# shield.net
KiCad netlist of a schematic drawn in EAGLE
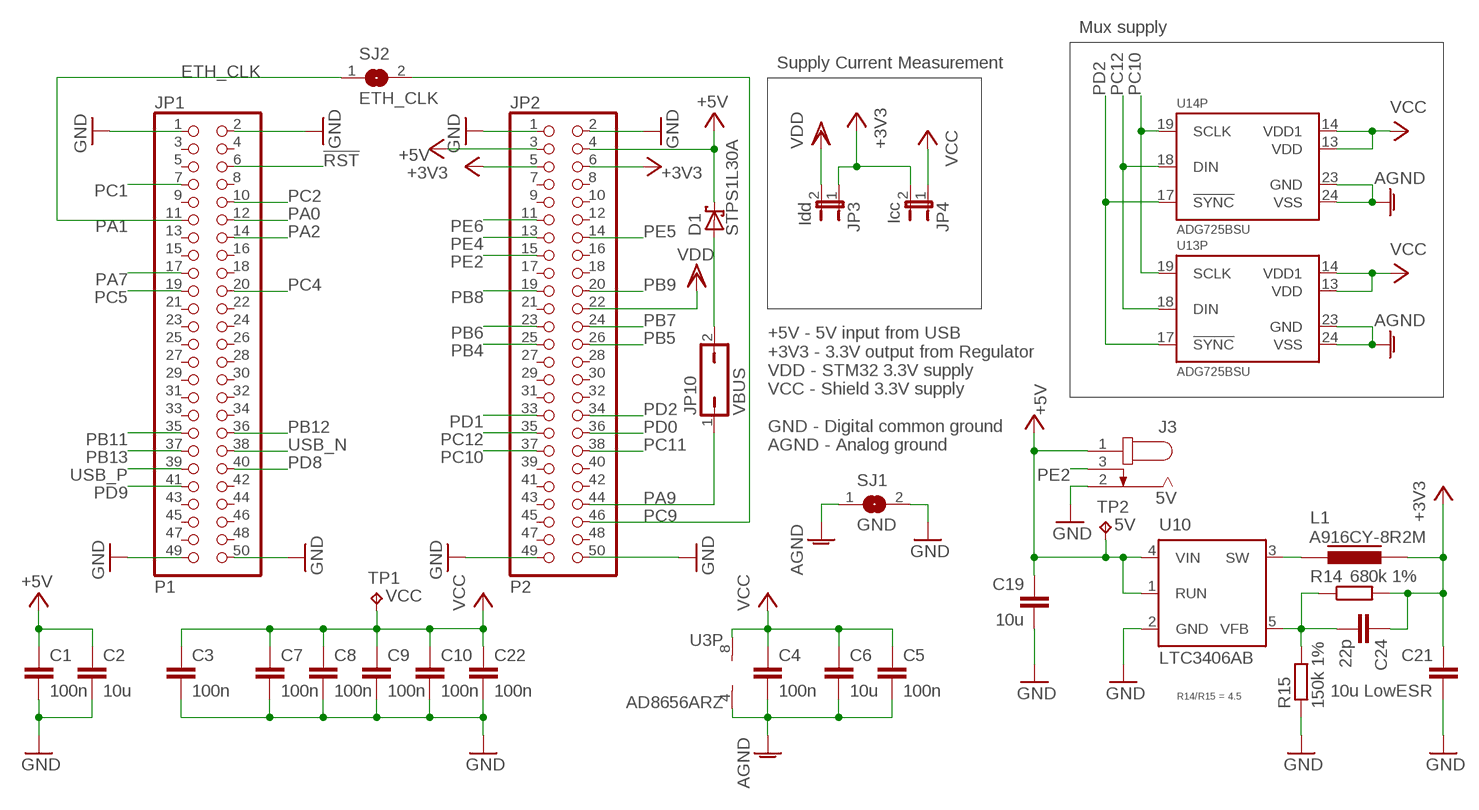
[diagram p0: schematic, sheet 1]
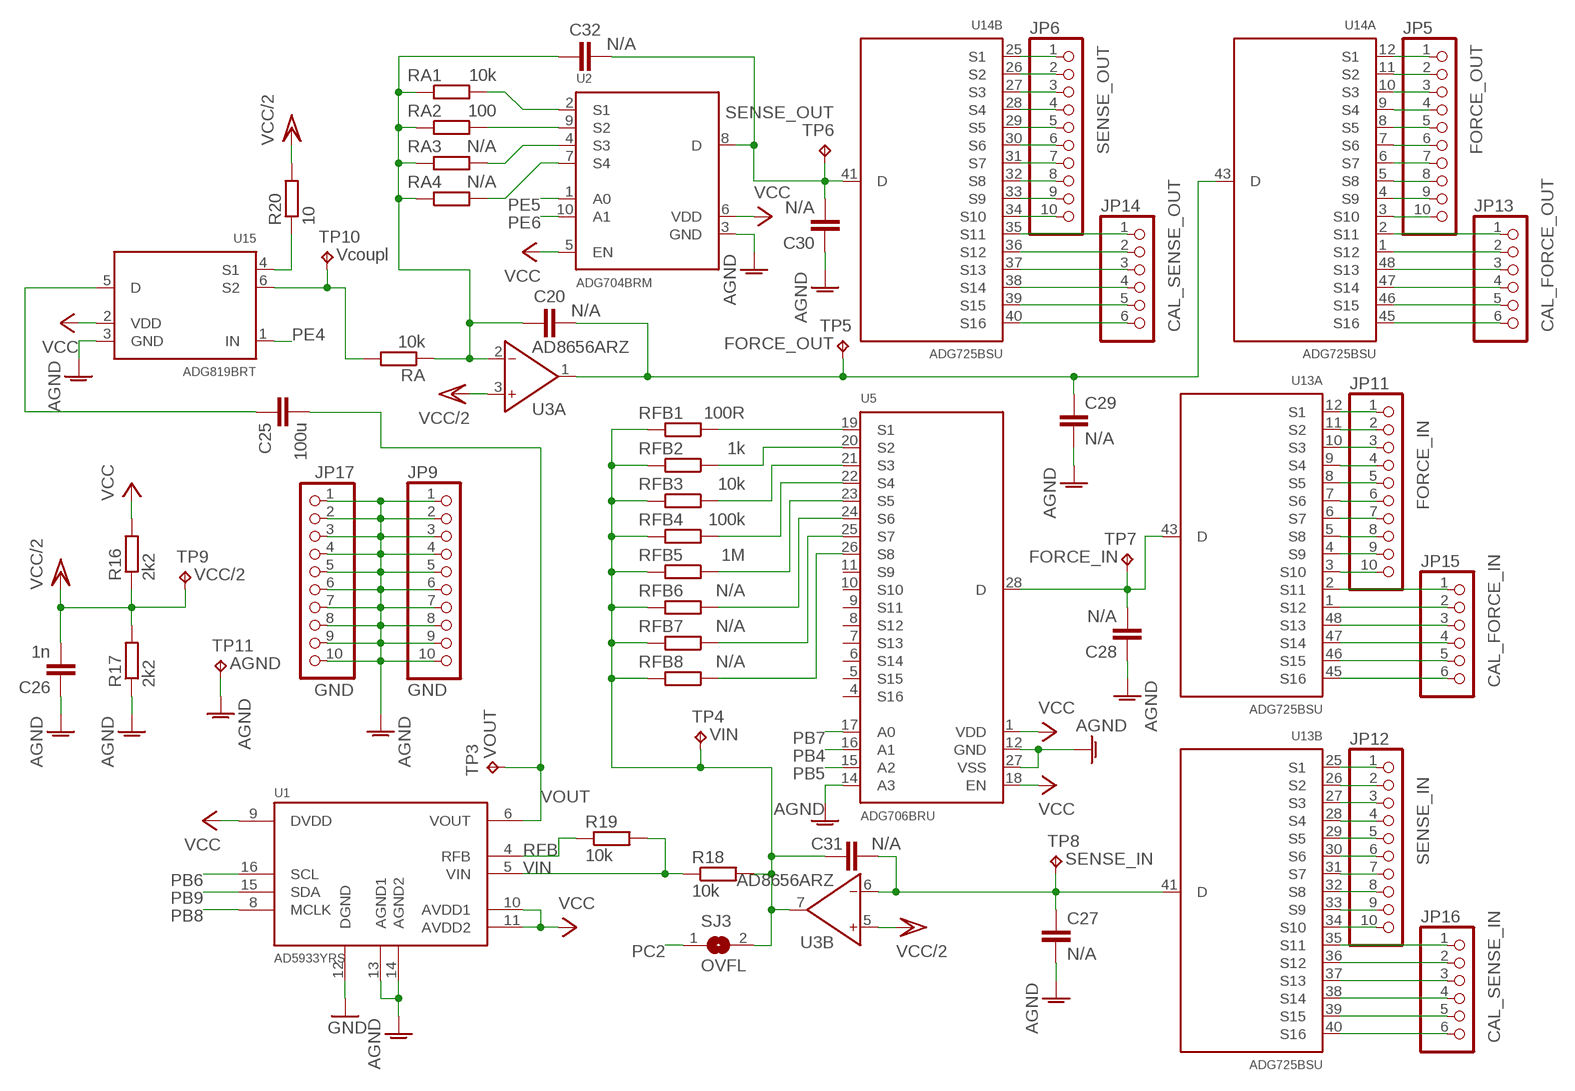
[diagram p1: schematic, sheet 2]
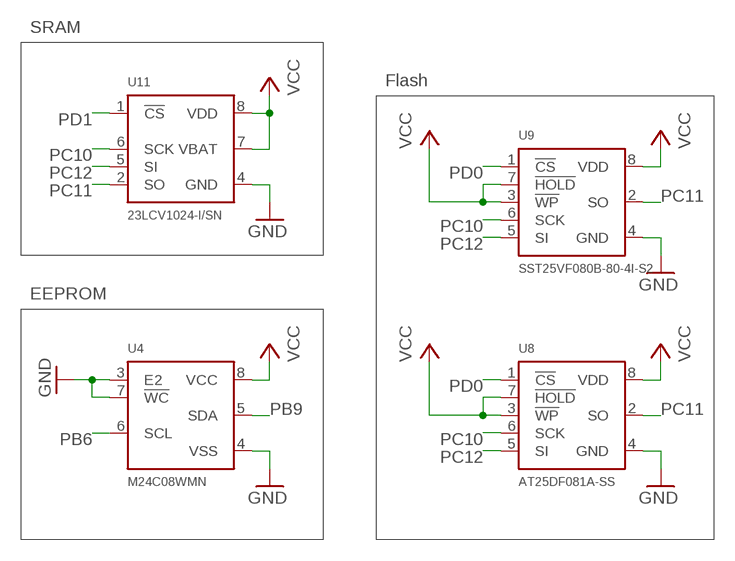
[diagram p2: schematic, sheet 3]
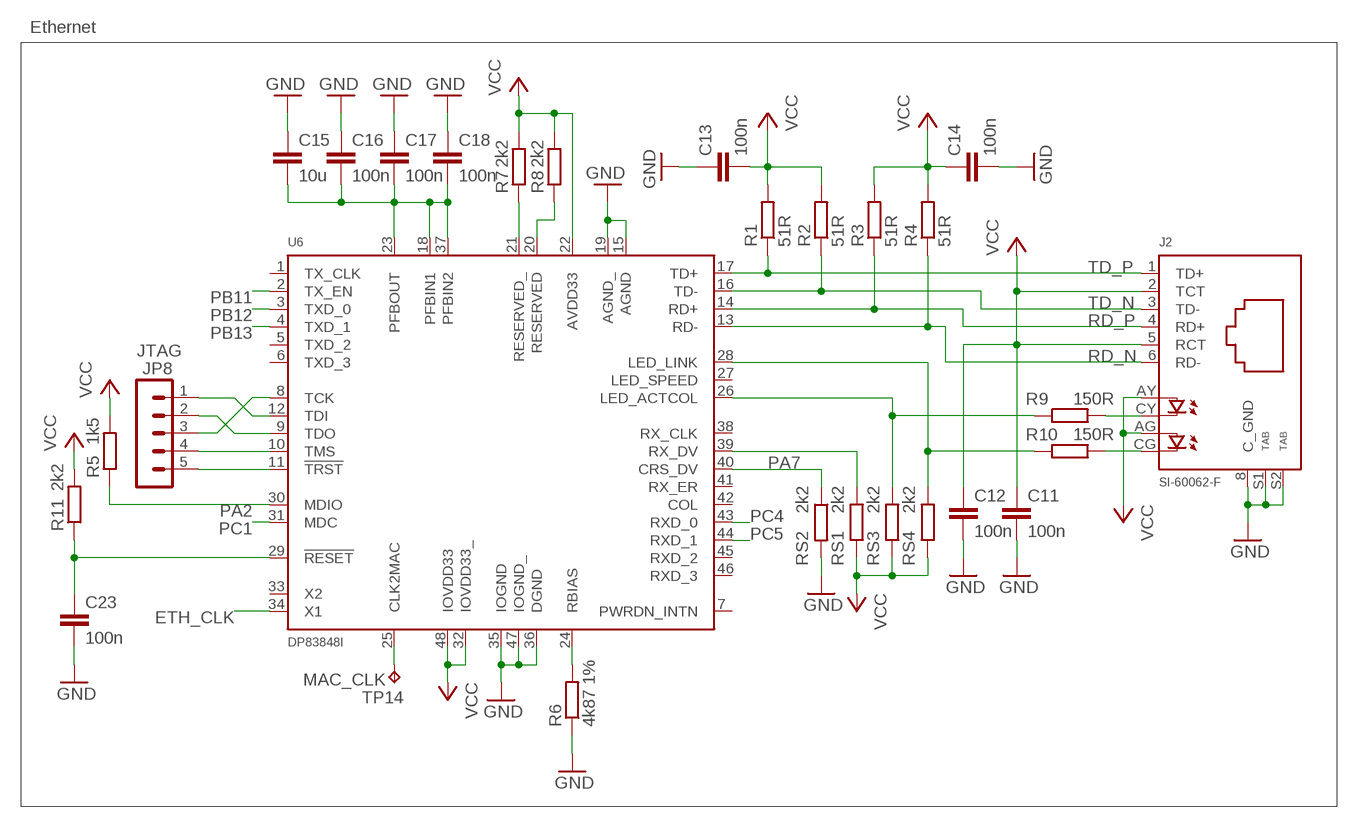
[diagram p3: schematic, sheet 4]
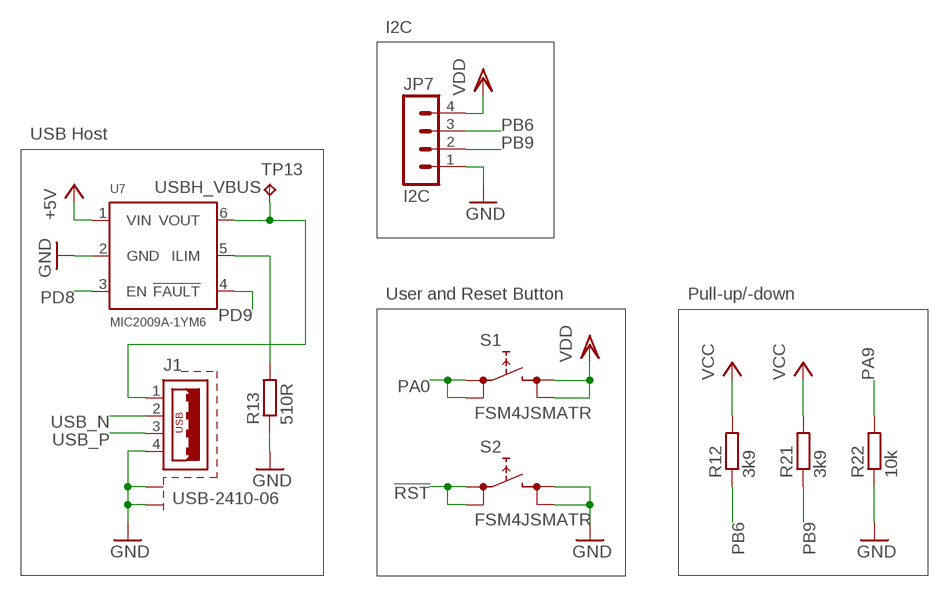
[diagram p4: schematic, sheet 5]

(export (version "E")
  (design (tool "Eeschema 10.0.6"))
  (components
    (comp (ref "J1")
      (value "USB-2410-06")
      (footprint "eagle-import:USB-2410-06")
      (libsource (lib "eagle-import") (part "USB-2410-06"))
    )
    (comp (ref "JP7")
      (value "I2C")
      (footprint "eagle-import:MA04-1")
      (libsource (lib "eagle-import") (part "MA04-1"))
    )
    (comp (ref "R12")
      (value "3k9")
      (footprint "eagle-import:R0603")
      (libsource (lib "eagle-import") (part "R-EU_R0603"))
    )
    (comp (ref "R13")
      (value "510R")
      (footprint "eagle-import:R0603")
      (libsource (lib "eagle-import") (part "R-EU_R0603"))
    )
    (comp (ref "R21")
      (value "3k9")
      (footprint "eagle-import:R0603")
      (libsource (lib "eagle-import") (part "R-EU_R0603"))
    )
    (comp (ref "R22")
      (value "10k")
      (footprint "eagle-import:R0603")
      (libsource (lib "eagle-import") (part "R-EU_R0603"))
    )
    (comp (ref "S1")
      (value "FSM4JSMATR")
      (footprint "eagle-import:FSM")
      (libsource (lib "eagle-import") (part "FSM4JSMATR"))
    )
    (comp (ref "S2")
      (value "FSM4JSMATR")
      (footprint "eagle-import:FSM")
      (libsource (lib "eagle-import") (part "FSM4JSMATR"))
    )
    (comp (ref "TP13")
      (value "TPTP20R")
      (footprint "eagle-import:TP20R")
      (fields (field (name "TP_SIGNAL_NAME") "USBH_VBUS"))
      (libsource (lib "eagle-import") (part "TPTP20R"))
    )
    (comp (ref "U7")
      (value "MIC2009A-1YM6")
      (footprint "eagle-import:SOT23-6")
      (libsource (lib "eagle-import") (part "MIC2009A-1YM6"))
    )
    (comp (ref "C1")
      (value "100n")
      (footprint "eagle-import:C0603")
      (libsource (lib "eagle-import") (part "C-EUC0603"))
    )
    (comp (ref "C2")
      (value "10u")
      (footprint "eagle-import:C0603")
      (libsource (lib "eagle-import") (part "C-EUC0603"))
    )
    (comp (ref "C3")
      (value "100n")
      (footprint "eagle-import:C0603")
      (libsource (lib "eagle-import") (part "C-EUC0603"))
    )
    (comp (ref "C4")
      (value "100n")
      (footprint "eagle-import:C0603")
      (libsource (lib "eagle-import") (part "C-EUC0603"))
    )
    (comp (ref "C5")
      (value "100n")
      (footprint "eagle-import:C0603")
      (libsource (lib "eagle-import") (part "C-EUC0603"))
    )
    (comp (ref "C6")
      (value "10u")
      (footprint "eagle-import:C0603")
      (libsource (lib "eagle-import") (part "C-EUC0603"))
    )
    (comp (ref "C7")
      (value "100n")
      (footprint "eagle-import:C0603")
      (libsource (lib "eagle-import") (part "C-EUC0603"))
    )
    (comp (ref "C8")
      (value "100n")
      (footprint "eagle-import:C0603")
      (libsource (lib "eagle-import") (part "C-EUC0603"))
    )
    (comp (ref "C9")
      (value "100n")
      (footprint "eagle-import:C0603")
      (libsource (lib "eagle-import") (part "C-EUC0603"))
    )
    (comp (ref "C10")
      (value "100n")
      (footprint "eagle-import:C0603")
      (libsource (lib "eagle-import") (part "C-EUC0603"))
    )
    (comp (ref "C19")
      (value "10u")
      (footprint "eagle-import:C3216")
      (libsource (lib "eagle-import") (part "C-EUC3216"))
    )
    (comp (ref "C21")
      (value "10u LowESR")
      (footprint "eagle-import:C3216")
      (libsource (lib "eagle-import") (part "C-EUC3216"))
    )
    (comp (ref "C22")
      (value "100n")
      (footprint "eagle-import:C0603")
      (libsource (lib "eagle-import") (part "C-EUC0603"))
    )
    (comp (ref "C24")
      (value "22p")
      (footprint "eagle-import:C0603")
      (libsource (lib "eagle-import") (part "C-EUC0603"))
    )
    (comp (ref "D1")
      (value "STPS1L30A")
      (footprint "eagle-import:DO214AC")
      (libsource (lib "eagle-import") (part "STPS1L30A"))
    )
    (comp (ref "J3")
      (value "5V")
      (footprint "eagle-import:JACK-SMD2.5")
      (libsource (lib "eagle-import") (part "JACK-PLUG-S2.5"))
    )
    (comp (ref "JP1")
      (value "P1")
      (footprint "eagle-import:2X25-F")
      (libsource (lib "eagle-import") (part "PINHD-2X25-F"))
    )
    (comp (ref "JP2")
      (value "P2")
      (footprint "eagle-import:2X25-F")
      (libsource (lib "eagle-import") (part "PINHD-2X25-F"))
    )
    (comp (ref "JP3")
      (value "Idd")
      (footprint "eagle-import:JP1")
      (libsource (lib "eagle-import") (part "JP1E"))
    )
    (comp (ref "JP4")
      (value "Icc")
      (footprint "eagle-import:JP1")
      (libsource (lib "eagle-import") (part "JP1E"))
    )
    (comp (ref "JP10")
      (value "VBUS")
      (footprint "eagle-import:JP1")
      (libsource (lib "eagle-import") (part "JP1Q"))
    )
    (comp (ref "L1")
      (value "A916CY-8R2M")
      (footprint "eagle-import:D63CB")
      (libsource (lib "eagle-import") (part "A916CY-8R2M"))
    )
    (comp (ref "R14")
      (value "680k 1%")
      (footprint "eagle-import:R0603")
      (libsource (lib "eagle-import") (part "R-EU_R0603"))
    )
    (comp (ref "R15")
      (value "150k 1%")
      (footprint "eagle-import:R0603")
      (libsource (lib "eagle-import") (part "R-EU_R0603"))
    )
    (comp (ref "SJ1")
      (value "GND")
      (footprint "eagle-import:SJ")
      (libsource (lib "eagle-import") (part "SJ"))
    )
    (comp (ref "SJ2")
      (value "ETH_CLK")
      (footprint "eagle-import:SJ")
      (libsource (lib "eagle-import") (part "SJ"))
    )
    (comp (ref "TP1")
      (value "TPTP20R")
      (footprint "eagle-import:TP20R")
      (fields (field (name "TP_SIGNAL_NAME") "VCC"))
      (libsource (lib "eagle-import") (part "TPTP20R"))
    )
    (comp (ref "TP2")
      (value "TPTP20R")
      (footprint "eagle-import:TP20R")
      (fields (field (name "TP_SIGNAL_NAME") "5V"))
      (libsource (lib "eagle-import") (part "TPTP20R"))
    )
    (comp (ref "U3")
      (value "AD8656ARZ")
      (footprint "eagle-import:SOIC8")
      (libsource (lib "eagle-import") (part "AD8656ZAR"))
    )
    (comp (ref "U10")
      (value "LTC3406AB")
      (footprint "eagle-import:TSOT23-5")
      (libsource (lib "eagle-import") (part "LTC3406AB"))
    )
    (comp (ref "U13")
      (value "ADG725BSU")
      (footprint "eagle-import:TQFP48")
      (libsource (lib "eagle-import") (part "ADG725SUB"))
    )
    (comp (ref "U14")
      (value "ADG725BSU")
      (footprint "eagle-import:TQFP48")
      (libsource (lib "eagle-import") (part "ADG725SUB"))
    )
    (comp (ref "C11")
      (value "100n")
      (footprint "eagle-import:C0603")
      (libsource (lib "eagle-import") (part "C-EUC0603"))
    )
    (comp (ref "C12")
      (value "100n")
      (footprint "eagle-import:C0603")
      (libsource (lib "eagle-import") (part "C-EUC0603"))
    )
    (comp (ref "C13")
      (value "100n")
      (footprint "eagle-import:C0603")
      (libsource (lib "eagle-import") (part "C-EUC0603"))
    )
    (comp (ref "C14")
      (value "100n")
      (footprint "eagle-import:C0603")
      (libsource (lib "eagle-import") (part "C-EUC0603"))
    )
    (comp (ref "C15")
      (value "10u")
      (footprint "eagle-import:C0603")
      (libsource (lib "eagle-import") (part "C-EUC0603"))
    )
    (comp (ref "C16")
      (value "100n")
      (footprint "eagle-import:C0603")
      (libsource (lib "eagle-import") (part "C-EUC0603"))
    )
    (comp (ref "C17")
      (value "100n")
      (footprint "eagle-import:C0603")
      (libsource (lib "eagle-import") (part "C-EUC0603"))
    )
    (comp (ref "C18")
      (value "100n")
      (footprint "eagle-import:C0603")
      (libsource (lib "eagle-import") (part "C-EUC0603"))
    )
    (comp (ref "C23")
      (value "100n")
      (footprint "eagle-import:C0603")
      (libsource (lib "eagle-import") (part "C-EUC0603"))
    )
    (comp (ref "J2")
      (value "SI-60062-F")
      (footprint "eagle-import:SI-60062-F")
      (libsource (lib "eagle-import") (part "SI-60062-F"))
    )
    (comp (ref "JP8")
      (value "JTAG")
      (footprint "eagle-import:MA05-1")
      (libsource (lib "eagle-import") (part "MA05-1"))
    )
    (comp (ref "R1")
      (value "51R")
      (footprint "eagle-import:R0603")
      (libsource (lib "eagle-import") (part "R-EU_R0603"))
    )
    (comp (ref "R2")
      (value "51R")
      (footprint "eagle-import:R0603")
      (libsource (lib "eagle-import") (part "R-EU_R0603"))
    )
    (comp (ref "R3")
      (value "51R")
      (footprint "eagle-import:R0603")
      (libsource (lib "eagle-import") (part "R-EU_R0603"))
    )
    (comp (ref "R4")
      (value "51R")
      (footprint "eagle-import:R0603")
      (libsource (lib "eagle-import") (part "R-EU_R0603"))
    )
    (comp (ref "R5")
      (value "1k5")
      (footprint "eagle-import:R0603")
      (libsource (lib "eagle-import") (part "R-EU_R0603"))
    )
    (comp (ref "R6")
      (value "4k87 1%")
      (footprint "eagle-import:R0603")
      (libsource (lib "eagle-import") (part "R-EU_R0603"))
    )
    (comp (ref "R7")
      (value "2k2")
      (footprint "eagle-import:R0603")
      (libsource (lib "eagle-import") (part "R-EU_R0603"))
    )
    (comp (ref "R8")
      (value "2k2")
      (footprint "eagle-import:R0603")
      (libsource (lib "eagle-import") (part "R-EU_R0603"))
    )
    (comp (ref "R9")
      (value "150R")
      (footprint "eagle-import:R0603")
      (libsource (lib "eagle-import") (part "R-EU_R0603"))
    )
    (comp (ref "R10")
      (value "150R")
      (footprint "eagle-import:R0603")
      (libsource (lib "eagle-import") (part "R-EU_R0603"))
    )
    (comp (ref "R11")
      (value "2k2")
      (footprint "eagle-import:R0603")
      (libsource (lib "eagle-import") (part "R-EU_R0603"))
    )
    (comp (ref "RS1")
      (value "2k2")
      (footprint "eagle-import:R0603")
      (libsource (lib "eagle-import") (part "R-EU_R0603"))
    )
    (comp (ref "RS2")
      (value "2k2")
      (footprint "eagle-import:R0603")
      (libsource (lib "eagle-import") (part "R-EU_R0603"))
    )
    (comp (ref "RS3")
      (value "2k2")
      (footprint "eagle-import:R0603")
      (libsource (lib "eagle-import") (part "R-EU_R0603"))
    )
    (comp (ref "RS4")
      (value "2k2")
      (footprint "eagle-import:R0603")
      (libsource (lib "eagle-import") (part "R-EU_R0603"))
    )
    (comp (ref "TP14")
      (value "TPTP20R")
      (footprint "eagle-import:TP20R")
      (fields (field (name "TP_SIGNAL_NAME") "MAC_CLK"))
      (libsource (lib "eagle-import") (part "TPTP20R"))
    )
    (comp (ref "U6")
      (value "DP83848I")
      (footprint "eagle-import:LQFP48")
      (fields (field (name "MPN") "DP83848IVV"))
      (libsource (lib "eagle-import") (part "DP83848I"))
    )
    (comp (ref "U4")
      (value "M24C08WMN")
      (footprint "eagle-import:SO8")
      (libsource (lib "eagle-import") (part "M24C08MNW"))
    )
    (comp (ref "U8")
      (value "AT25DF081A-SS")
      (footprint "eagle-import:SO8")
      (libsource (lib "eagle-import") (part "AT25DF081A-SS"))
    )
    (comp (ref "U9")
      (value "SST25VF080B-80-4I-S2")
      (footprint "eagle-import:SOIC8")
      (libsource (lib "eagle-import") (part "SST25VF080B-S2-80-4I"))
    )
    (comp (ref "U11")
      (value "23LCV1024-I/SN")
      (footprint "eagle-import:SO8")
      (libsource (lib "eagle-import") (part "23LCV1024/SN-I"))
    )
    (comp (ref "C20")
      (value "N/A")
      (footprint "eagle-import:C0603")
      (libsource (lib "eagle-import") (part "C-EUC0603"))
    )
    (comp (ref "C25")
      (value "100u")
      (footprint "eagle-import:C1206")
      (libsource (lib "eagle-import") (part "C-EUC1206"))
    )
    (comp (ref "C26")
      (value "1n")
      (footprint "eagle-import:C0603")
      (libsource (lib "eagle-import") (part "C-EUC0603"))
    )
    (comp (ref "C27")
      (value "N/A")
      (footprint "eagle-import:C0805")
      (libsource (lib "eagle-import") (part "C-EUC0805"))
    )
    (comp (ref "C28")
      (value "N/A")
      (footprint "eagle-import:C0805")
      (libsource (lib "eagle-import") (part "C-EUC0805"))
    )
    (comp (ref "C29")
      (value "N/A")
      (footprint "eagle-import:C0805")
      (libsource (lib "eagle-import") (part "C-EUC0805"))
    )
    (comp (ref "C30")
      (value "N/A")
      (footprint "eagle-import:C0805")
      (libsource (lib "eagle-import") (part "C-EUC0805"))
    )
    (comp (ref "C31")
      (value "N/A")
      (footprint "eagle-import:C0603")
      (libsource (lib "eagle-import") (part "C-EUC0603"))
    )
    (comp (ref "C32")
      (value "N/A")
      (footprint "eagle-import:C0603")
      (libsource (lib "eagle-import") (part "C-EUC0603"))
    )
    (comp (ref "JP5")
      (value "FORCE_OUT")
      (footprint "eagle-import:1X10")
      (libsource (lib "eagle-import") (part "PINHD-1X10"))
    )
    (comp (ref "JP6")
      (value "SENSE_OUT")
      (footprint "eagle-import:1X10")
      (libsource (lib "eagle-import") (part "PINHD-1X10"))
    )
    (comp (ref "JP9")
      (value "GND")
      (footprint "eagle-import:1X10")
      (libsource (lib "eagle-import") (part "PINHD-1X10"))
    )
    (comp (ref "JP11")
      (value "FORCE_IN")
      (footprint "eagle-import:1X10")
      (libsource (lib "eagle-import") (part "PINHD-1X10"))
    )
    (comp (ref "JP12")
      (value "SENSE_IN")
      (footprint "eagle-import:1X10")
      (libsource (lib "eagle-import") (part "PINHD-1X10"))
    )
    (comp (ref "JP13")
      (value "CAL_FORCE_OUT")
      (footprint "eagle-import:1X06")
      (libsource (lib "eagle-import") (part "PINHD-1X6"))
    )
    (comp (ref "JP14")
      (value "CAL_SENSE_OUT")
      (footprint "eagle-import:1X06")
      (libsource (lib "eagle-import") (part "PINHD-1X6"))
    )
    (comp (ref "JP15")
      (value "CAL_FORCE_IN")
      (footprint "eagle-import:1X06")
      (libsource (lib "eagle-import") (part "PINHD-1X6"))
    )
    (comp (ref "JP16")
      (value "CAL_SENSE_IN")
      (footprint "eagle-import:1X06")
      (libsource (lib "eagle-import") (part "PINHD-1X6"))
    )
    (comp (ref "JP17")
      (value "GND")
      (footprint "eagle-import:1X10")
      (libsource (lib "eagle-import") (part "PINHD-1X10"))
    )
    (comp (ref "R16")
      (value "2k2")
      (footprint "eagle-import:R0603")
      (libsource (lib "eagle-import") (part "R-EU_R0603"))
    )
    (comp (ref "R17")
      (value "2k2")
      (footprint "eagle-import:R0603")
      (libsource (lib "eagle-import") (part "R-EU_R0603"))
    )
    (comp (ref "R18")
      (value "10k")
      (footprint "eagle-import:R0603")
      (libsource (lib "eagle-import") (part "R-EU_R0603"))
    )
    (comp (ref "R19")
      (value "10k")
      (footprint "eagle-import:R0603")
      (libsource (lib "eagle-import") (part "R-EU_R0603"))
    )
    (comp (ref "R20")
      (value "10")
      (footprint "eagle-import:R0603")
      (libsource (lib "eagle-import") (part "R-EU_R0603"))
    )
    (comp (ref "RA")
      (value "10k")
      (footprint "eagle-import:R0603")
      (libsource (lib "eagle-import") (part "R-EU_R0603"))
    )
    (comp (ref "RA1")
      (value "10k")
      (footprint "eagle-import:R0603")
      (libsource (lib "eagle-import") (part "R-EU_R0603"))
    )
    (comp (ref "RA2")
      (value "100")
      (footprint "eagle-import:R0603")
      (libsource (lib "eagle-import") (part "R-EU_R0603"))
    )
    (comp (ref "RA3")
      (value "N/A")
      (footprint "eagle-import:R0603")
      (libsource (lib "eagle-import") (part "R-EU_R0603"))
    )
    (comp (ref "RA4")
      (value "N/A")
      (footprint "eagle-import:R0603")
      (libsource (lib "eagle-import") (part "R-EU_R0603"))
    )
    (comp (ref "RFB1")
      (value "100R")
      (footprint "eagle-import:R0603")
      (libsource (lib "eagle-import") (part "R-EU_R0603"))
    )
    (comp (ref "RFB2")
      (value "1k")
      (footprint "eagle-import:R0603")
      (libsource (lib "eagle-import") (part "R-EU_R0603"))
    )
    (comp (ref "RFB3")
      (value "10k")
      (footprint "eagle-import:R0603")
      (libsource (lib "eagle-import") (part "R-EU_R0603"))
    )
    (comp (ref "RFB4")
      (value "100k")
      (footprint "eagle-import:R0603")
      (libsource (lib "eagle-import") (part "R-EU_R0603"))
    )
    (comp (ref "RFB5")
      (value "1M")
      (footprint "eagle-import:R0603")
      (libsource (lib "eagle-import") (part "R-EU_R0603"))
    )
    (comp (ref "RFB6")
      (value "N/A")
      (footprint "eagle-import:R0603")
      (libsource (lib "eagle-import") (part "R-EU_R0603"))
    )
    (comp (ref "RFB7")
      (value "N/A")
      (footprint "eagle-import:R0603")
      (libsource (lib "eagle-import") (part "R-EU_R0603"))
    )
    (comp (ref "RFB8")
      (value "N/A")
      (footprint "eagle-import:R0603")
      (libsource (lib "eagle-import") (part "R-EU_R0603"))
    )
    (comp (ref "SJ3")
      (value "OVFL")
      (footprint "eagle-import:SJ")
      (libsource (lib "eagle-import") (part "SJ"))
    )
    (comp (ref "TP3")
      (value "TPTP20R")
      (footprint "eagle-import:TP20R")
      (fields (field (name "TP_SIGNAL_NAME") "VOUT"))
      (libsource (lib "eagle-import") (part "TPTP20R"))
    )
    (comp (ref "TP4")
      (value "TPTP20R")
      (footprint "eagle-import:TP20R")
      (fields (field (name "TP_SIGNAL_NAME") "VIN"))
      (libsource (lib "eagle-import") (part "TPTP20R"))
    )
    (comp (ref "TP5")
      (value "TPTP20R")
      (footprint "eagle-import:TP20R")
      (fields (field (name "TP_SIGNAL_NAME") "FORCE_OUT"))
      (libsource (lib "eagle-import") (part "TPTP20R"))
    )
    (comp (ref "TP6")
      (value "TPTP20R")
      (footprint "eagle-import:TP20R")
      (fields (field (name "TP_SIGNAL_NAME") "SENSE_OUT"))
      (libsource (lib "eagle-import") (part "TPTP20R"))
    )
    (comp (ref "TP7")
      (value "TPTP20R")
      (footprint "eagle-import:TP20R")
      (fields (field (name "TP_SIGNAL_NAME") "FORCE_IN"))
      (libsource (lib "eagle-import") (part "TPTP20R"))
    )
    (comp (ref "TP8")
      (value "TPTP20R")
      (footprint "eagle-import:TP20R")
      (fields (field (name "TP_SIGNAL_NAME") "SENSE_IN"))
      (libsource (lib "eagle-import") (part "TPTP20R"))
    )
    (comp (ref "TP9")
      (value "TPTP20R")
      (footprint "eagle-import:TP20R")
      (fields (field (name "TP_SIGNAL_NAME") "VCC/2"))
      (libsource (lib "eagle-import") (part "TPTP20R"))
    )
    (comp (ref "TP10")
      (value "TPTP20R")
      (footprint "eagle-import:TP20R")
      (fields (field (name "TP_SIGNAL_NAME") "Vcoupl"))
      (libsource (lib "eagle-import") (part "TPTP20R"))
    )
    (comp (ref "TP11")
      (value "TPPAD1-13")
      (footprint "eagle-import:P1-13")
      (fields (field (name "TP_SIGNAL_NAME") "AGND"))
      (libsource (lib "eagle-import") (part "TPPAD1-13"))
    )
    (comp (ref "U1")
      (value "AD5933YRS")
      (footprint "eagle-import:SSOP16")
      (libsource (lib "eagle-import") (part "AD5933RSY"))
    )
    (comp (ref "U2")
      (value "ADG704BRM")
      (footprint "eagle-import:MSOP10")
      (libsource (lib "eagle-import") (part "ADG704RMB"))
    )
    (comp (ref "U5")
      (value "ADG706BRU")
      (footprint "eagle-import:TSSOP28")
      (libsource (lib "eagle-import") (part "ADG706RUB"))
    )
    (comp (ref "U15")
      (value "ADG819BRT")
      (footprint "eagle-import:SOT23-6")
      (libsource (lib "eagle-import") (part "ADG819RTB"))
    )
  )
  (nets
    (net (code "1") (name "+3V3") (class "Default")
      (node (ref "C21") (pin "1") (pinfunction "1_1") (pintype "passive"))
      (node (ref "C24") (pin "1") (pinfunction "1_1") (pintype "passive"))
      (node (ref "JP2") (pin "5") (pinfunction "5_5") (pintype "passive"))
      (node (ref "JP2") (pin "6") (pinfunction "6_6") (pintype "passive"))
      (node (ref "JP3") (pin "1") (pinfunction "1_1") (pintype "passive"))
      (node (ref "JP4") (pin "2") (pinfunction "2_2") (pintype "passive"))
      (node (ref "L1") (pin "2") (pinfunction "2_2") (pintype "passive"))
      (node (ref "R14") (pin "2") (pinfunction "2_2") (pintype "passive"))
    )
    (net (code "2") (name "+5V") (class "Default")
      (node (ref "C1") (pin "1") (pinfunction "1_1") (pintype "passive"))
      (node (ref "C19") (pin "1") (pinfunction "1_1") (pintype "passive"))
      (node (ref "C2") (pin "1") (pinfunction "1_1") (pintype "passive"))
      (node (ref "D1") (pin "C") (pinfunction "C_C") (pintype "passive"))
      (node (ref "J3") (pin "1") (pinfunction "1_1") (pintype "passive"))
      (node (ref "JP2") (pin "3") (pinfunction "3_3") (pintype "passive"))
      (node (ref "JP2") (pin "4") (pinfunction "4_4") (pintype "passive"))
      (node (ref "TP2") (pin "TP") (pinfunction "TP_TP") (pintype "input"))
      (node (ref "U10") (pin "1") (pinfunction "RUN_1") (pintype "input"))
      (node (ref "U10") (pin "4") (pinfunction "VIN_4") (pintype "power_in"))
      (node (ref "U7") (pin "1") (pinfunction "VIN_1") (pintype "power_in"))
    )
    (net (code "3") (name "AGND") (class "Default")
      (node (ref "C26") (pin "1") (pinfunction "1_1") (pintype "passive"))
      (node (ref "C27") (pin "2") (pinfunction "2_2") (pintype "passive"))
      (node (ref "C28") (pin "1") (pinfunction "1_1") (pintype "passive"))
      (node (ref "C29") (pin "2") (pinfunction "2_2") (pintype "passive"))
      (node (ref "C30") (pin "1") (pinfunction "1_1") (pintype "passive"))
      (node (ref "C4") (pin "2") (pinfunction "2_2") (pintype "passive"))
      (node (ref "C5") (pin "2") (pinfunction "2_2") (pintype "passive"))
      (node (ref "C6") (pin "2") (pinfunction "2_2") (pintype "passive"))
      (node (ref "JP17") (pin "1") (pinfunction "1_1") (pintype "passive"))
      (node (ref "JP17") (pin "10") (pinfunction "10_10") (pintype "passive"))
      (node (ref "JP17") (pin "2") (pinfunction "2_2") (pintype "passive"))
      (node (ref "JP17") (pin "3") (pinfunction "3_3") (pintype "passive"))
      (node (ref "JP17") (pin "4") (pinfunction "4_4") (pintype "passive"))
      (node (ref "JP17") (pin "5") (pinfunction "5_5") (pintype "passive"))
      (node (ref "JP17") (pin "6") (pinfunction "6_6") (pintype "passive"))
      (node (ref "JP17") (pin "7") (pinfunction "7_7") (pintype "passive"))
      (node (ref "JP17") (pin "8") (pinfunction "8_8") (pintype "passive"))
      (node (ref "JP17") (pin "9") (pinfunction "9_9") (pintype "passive"))
      (node (ref "JP9") (pin "1") (pinfunction "1_1") (pintype "passive"))
      (node (ref "JP9") (pin "10") (pinfunction "10_10") (pintype "passive"))
      (node (ref "JP9") (pin "2") (pinfunction "2_2") (pintype "passive"))
      (node (ref "JP9") (pin "3") (pinfunction "3_3") (pintype "passive"))
      (node (ref "JP9") (pin "4") (pinfunction "4_4") (pintype "passive"))
      (node (ref "JP9") (pin "5") (pinfunction "5_5") (pintype "passive"))
      (node (ref "JP9") (pin "6") (pinfunction "6_6") (pintype "passive"))
      (node (ref "JP9") (pin "7") (pinfunction "7_7") (pintype "passive"))
      (node (ref "JP9") (pin "8") (pinfunction "8_8") (pintype "passive"))
      (node (ref "JP9") (pin "9") (pinfunction "9_9") (pintype "passive"))
      (node (ref "R17") (pin "1") (pinfunction "1_1") (pintype "passive"))
      (node (ref "SJ1") (pin "1") (pinfunction "1_1") (pintype "passive"))
      (node (ref "TP11") (pin "TP") (pinfunction "TP_TP") (pintype "input"))
      (node (ref "U1") (pin "13") (pinfunction "AGND1_13") (pintype "bidirectional"))
      (node (ref "U1") (pin "14") (pinfunction "AGND2_14") (pintype "bidirectional"))
      (node (ref "U13") (pin "23") (pinfunction "GND_23") (pintype "power_in"))
      (node (ref "U13") (pin "24") (pinfunction "VSS_24") (pintype "power_in"))
      (node (ref "U14") (pin "23") (pinfunction "GND_23") (pintype "power_in"))
      (node (ref "U14") (pin "24") (pinfunction "VSS_24") (pintype "power_in"))
      (node (ref "U15") (pin "3") (pinfunction "GND_3") (pintype "power_in"))
      (node (ref "U2") (pin "3") (pinfunction "GND_3") (pintype "power_in"))
      (node (ref "U3") (pin "4") (pinfunction "V-_4") (pintype "power_in"))
      (node (ref "U5") (pin "12") (pinfunction "GND_12") (pintype "power_in"))
      (node (ref "U5") (pin "14") (pinfunction "A3_14") (pintype "input"))
      (node (ref "U5") (pin "27") (pinfunction "VSS_27") (pintype "power_in"))
    )
    (net (code "4") (name "ETH_CLK") (class "Default")
      (node (ref "JP1") (pin "11") (pinfunction "11_11") (pintype "passive"))
      (node (ref "SJ2") (pin "1") (pinfunction "1_1") (pintype "passive"))
      (node (ref "U6") (pin "34") (pinfunction "X1_34") (pintype "input"))
    )
    (net (code "5") (name "GND") (class "Default")
      (node (ref "C1") (pin "2") (pinfunction "2_2") (pintype "passive"))
      (node (ref "C10") (pin "2") (pinfunction "2_2") (pintype "passive"))
      (node (ref "C11") (pin "2") (pinfunction "2_2") (pintype "passive"))
      (node (ref "C12") (pin "2") (pinfunction "2_2") (pintype "passive"))
      (node (ref "C13") (pin "1") (pinfunction "1_1") (pintype "passive"))
      (node (ref "C14") (pin "2") (pinfunction "2_2") (pintype "passive"))
      (node (ref "C15") (pin "1") (pinfunction "1_1") (pintype "passive"))
      (node (ref "C16") (pin "1") (pinfunction "1_1") (pintype "passive"))
      (node (ref "C17") (pin "1") (pinfunction "1_1") (pintype "passive"))
      (node (ref "C18") (pin "1") (pinfunction "1_1") (pintype "passive"))
      (node (ref "C19") (pin "2") (pinfunction "2_2") (pintype "passive"))
      (node (ref "C2") (pin "2") (pinfunction "2_2") (pintype "passive"))
      (node (ref "C21") (pin "2") (pinfunction "2_2") (pintype "passive"))
      (node (ref "C22") (pin "2") (pinfunction "2_2") (pintype "passive"))
      (node (ref "C23") (pin "2") (pinfunction "2_2") (pintype "passive"))
      (node (ref "C3") (pin "2") (pinfunction "2_2") (pintype "passive"))
      (node (ref "C7") (pin "2") (pinfunction "2_2") (pintype "passive"))
      (node (ref "C8") (pin "2") (pinfunction "2_2") (pintype "passive"))
      (node (ref "C9") (pin "2") (pinfunction "2_2") (pintype "passive"))
      (node (ref "J1") (pin "4") (pinfunction "GND_4") (pintype "passive"))
      (node (ref "J1") (pin "S1") (pinfunction "S1_S1") (pintype "passive"))
      (node (ref "J1") (pin "S2") (pinfunction "S2_S2") (pintype "passive"))
      (node (ref "J2") (pin "8") (pinfunction "C_GND_8") (pintype "passive"))
      (node (ref "J2") (pin "S1") (pinfunction "TAB1_S1") (pintype "passive"))
      (node (ref "J2") (pin "S2") (pinfunction "TAB2_S2") (pintype "passive"))
      (node (ref "J3") (pin "2") (pinfunction "3_2") (pintype "passive"))
      (node (ref "JP1") (pin "1") (pinfunction "1_1") (pintype "passive"))
      (node (ref "JP1") (pin "2") (pinfunction "2_2") (pintype "passive"))
      (node (ref "JP1") (pin "49") (pinfunction "49_49") (pintype "passive"))
      (node (ref "JP1") (pin "50") (pinfunction "50_50") (pintype "passive"))
      (node (ref "JP2") (pin "1") (pinfunction "1_1") (pintype "passive"))
      (node (ref "JP2") (pin "2") (pinfunction "2_2") (pintype "passive"))
      (node (ref "JP2") (pin "49") (pinfunction "49_49") (pintype "passive"))
      (node (ref "JP2") (pin "50") (pinfunction "50_50") (pintype "passive"))
      (node (ref "JP7") (pin "1") (pinfunction "1_1") (pintype "passive"))
      (node (ref "R13") (pin "1") (pinfunction "1_1") (pintype "passive"))
      (node (ref "R15") (pin "1") (pinfunction "1_1") (pintype "passive"))
      (node (ref "R22") (pin "1") (pinfunction "1_1") (pintype "passive"))
      (node (ref "R6") (pin "1") (pinfunction "1_1") (pintype "passive"))
      (node (ref "RS2") (pin "2") (pinfunction "2_2") (pintype "passive"))
      (node (ref "S2") (pin "3") (pinfunction "1_3") (pintype "passive"))
      (node (ref "S2") (pin "4") (pinfunction "1_4") (pintype "passive"))
      (node (ref "SJ1") (pin "2") (pinfunction "2_2") (pintype "passive"))
      (node (ref "U1") (pin "12") (pinfunction "DGND_12") (pintype "bidirectional"))
      (node (ref "U10") (pin "2") (pinfunction "GND_2") (pintype "power_in"))
      (node (ref "U11") (pin "4") (pinfunction "GND_4") (pintype "power_in"))
      (node (ref "U4") (pin "3") (pinfunction "E2_3") (pintype "input"))
      (node (ref "U4") (pin "4") (pinfunction "VSS_4") (pintype "power_in"))
      (node (ref "U4") (pin "7") (pinfunction "~{WC}_7") (pintype "input"))
      (node (ref "U6") (pin "15") (pinfunction "AGND_15") (pintype "power_in"))
      (node (ref "U6") (pin "19") (pinfunction "AGND__19") (pintype "power_in"))
      (node (ref "U6") (pin "35") (pinfunction "IOGND_35") (pintype "power_in"))
      (node (ref "U6") (pin "36") (pinfunction "DGND_36") (pintype "power_in"))
      (node (ref "U6") (pin "47") (pinfunction "IOGND__47") (pintype "power_in"))
      (node (ref "U7") (pin "2") (pinfunction "GND_2") (pintype "power_in"))
      (node (ref "U8") (pin "4") (pinfunction "GND_4") (pintype "power_in"))
      (node (ref "U9") (pin "4") (pinfunction "GND_4") (pintype "power_in"))
    )
    (net (code "6") (name "Net-(D1-PadA)") (class "Default")
      (node (ref "D1") (pin "A") (pinfunction "A_A") (pintype "passive"))
      (node (ref "JP10") (pin "2") (pinfunction "2_2") (pintype "passive"))
    )
    (net (code "7") (name "Net-(J1-VCC)") (class "Default")
      (node (ref "J1") (pin "1") (pinfunction "VCC_1") (pintype "passive"))
      (node (ref "TP13") (pin "TP") (pinfunction "TP_TP") (pintype "input"))
      (node (ref "U7") (pin "6") (pinfunction "VOUT_6") (pintype "power_in"))
    )
    (net (code "8") (name "Net-(J2-PadCG)") (class "Default")
      (node (ref "J2") (pin "CG") (pinfunction "CG_CG") (pintype "passive"))
      (node (ref "R10") (pin "2") (pinfunction "2_2") (pintype "passive"))
    )
    (net (code "9") (name "Net-(J2-PadCY)") (class "Default")
      (node (ref "J2") (pin "CY") (pinfunction "CY_CY") (pintype "passive"))
      (node (ref "R9") (pin "2") (pinfunction "2_2") (pintype "passive"))
    )
    (net (code "10") (name "Net-(U2-S1)") (class "Default")
      (node (ref "RA1") (pin "2") (pinfunction "2_2") (pintype "passive"))
      (node (ref "U2") (pin "2") (pinfunction "S1_2") (pintype "bidirectional"))
    )
    (net (code "11") (name "Net-(U2-S2)") (class "Default")
      (node (ref "RA2") (pin "2") (pinfunction "2_2") (pintype "passive"))
      (node (ref "U2") (pin "9") (pinfunction "S2_9") (pintype "bidirectional"))
    )
    (net (code "12") (name "Net-(U2-S3)") (class "Default")
      (node (ref "RA3") (pin "2") (pinfunction "2_2") (pintype "passive"))
      (node (ref "U2") (pin "4") (pinfunction "S3_4") (pintype "bidirectional"))
    )
    (net (code "13") (name "Net-(U2-S4)") (class "Default")
      (node (ref "RA4") (pin "2") (pinfunction "2_2") (pintype "passive"))
      (node (ref "U2") (pin "7") (pinfunction "S4_7") (pintype "bidirectional"))
    )
    (net (code "14") (name "Net-(U3A-IN-)") (class "Default")
      (node (ref "C20") (pin "1") (pinfunction "1_1") (pintype "passive"))
      (node (ref "C32") (pin "1") (pinfunction "1_1") (pintype "passive"))
      (node (ref "RA") (pin "1") (pinfunction "1_1") (pintype "passive"))
      (node (ref "RA1") (pin "1") (pinfunction "1_1") (pintype "passive"))
      (node (ref "RA2") (pin "1") (pinfunction "1_1") (pintype "passive"))
      (node (ref "RA3") (pin "1") (pinfunction "1_1") (pintype "passive"))
      (node (ref "RA4") (pin "1") (pinfunction "1_1") (pintype "passive"))
      (node (ref "U3") (pin "2") (pinfunction "IN-_2") (pintype "input"))
    )
    (net (code "15") (name "Net-(U3B-OUT)") (class "Default")
      (node (ref "C31") (pin "1") (pinfunction "1_1") (pintype "passive"))
      (node (ref "R18") (pin "2") (pinfunction "2_2") (pintype "passive"))
      (node (ref "RFB1") (pin "2") (pinfunction "2_2") (pintype "passive"))
      (node (ref "RFB2") (pin "2") (pinfunction "2_2") (pintype "passive"))
      (node (ref "RFB3") (pin "2") (pinfunction "2_2") (pintype "passive"))
      (node (ref "RFB4") (pin "2") (pinfunction "2_2") (pintype "passive"))
      (node (ref "RFB5") (pin "2") (pinfunction "2_2") (pintype "passive"))
      (node (ref "RFB6") (pin "2") (pinfunction "2_2") (pintype "passive"))
      (node (ref "RFB7") (pin "2") (pinfunction "2_2") (pintype "passive"))
      (node (ref "RFB8") (pin "2") (pinfunction "2_2") (pintype "passive"))
      (node (ref "SJ3") (pin "2") (pinfunction "2_2") (pintype "passive"))
      (node (ref "TP4") (pin "TP") (pinfunction "TP_TP") (pintype "input"))
      (node (ref "U3") (pin "7") (pinfunction "OUT_7") (pintype "output"))
    )
    (net (code "16") (name "Net-(U5-S1)") (class "Default")
      (node (ref "RFB1") (pin "1") (pinfunction "1_1") (pintype "passive"))
      (node (ref "U5") (pin "19") (pinfunction "S1_19") (pintype "bidirectional"))
    )
    (net (code "17") (name "Net-(U5-S2)") (class "Default")
      (node (ref "RFB2") (pin "1") (pinfunction "1_1") (pintype "passive"))
      (node (ref "U5") (pin "20") (pinfunction "S2_20") (pintype "bidirectional"))
    )
    (net (code "18") (name "Net-(U5-S3)") (class "Default")
      (node (ref "RFB3") (pin "1") (pinfunction "1_1") (pintype "passive"))
      (node (ref "U5") (pin "21") (pinfunction "S3_21") (pintype "bidirectional"))
    )
    (net (code "19") (name "Net-(U5-S4)") (class "Default")
      (node (ref "RFB4") (pin "1") (pinfunction "1_1") (pintype "passive"))
      (node (ref "U5") (pin "22") (pinfunction "S4_22") (pintype "bidirectional"))
    )
    (net (code "20") (name "Net-(U5-S5)") (class "Default")
      (node (ref "RFB5") (pin "1") (pinfunction "1_1") (pintype "passive"))
      (node (ref "U5") (pin "23") (pinfunction "S5_23") (pintype "bidirectional"))
    )
    (net (code "21") (name "Net-(U5-S6)") (class "Default")
      (node (ref "RFB6") (pin "1") (pinfunction "1_1") (pintype "passive"))
      (node (ref "U5") (pin "24") (pinfunction "S6_24") (pintype "bidirectional"))
    )
    (net (code "22") (name "Net-(U5-S7)") (class "Default")
      (node (ref "RFB7") (pin "1") (pinfunction "1_1") (pintype "passive"))
      (node (ref "U5") (pin "25") (pinfunction "S7_25") (pintype "bidirectional"))
    )
    (net (code "23") (name "Net-(U5-S8)") (class "Default")
      (node (ref "RFB8") (pin "1") (pinfunction "1_1") (pintype "passive"))
      (node (ref "U5") (pin "26") (pinfunction "S8_26") (pintype "bidirectional"))
    )
    (net (code "24") (name "Net-(U6-CLK2MAC)") (class "Default")
      (node (ref "TP14") (pin "TP") (pinfunction "TP_TP") (pintype "input"))
      (node (ref "U6") (pin "25") (pinfunction "CLK2MAC_25") (pintype "output"))
    )
    (net (code "25") (name "Net-(U6-LED_ACTCOL)") (class "Default")
      (node (ref "R9") (pin "1") (pinfunction "1_1") (pintype "passive"))
      (node (ref "RS3") (pin "2") (pinfunction "2_2") (pintype "passive"))
      (node (ref "U6") (pin "26") (pinfunction "LED_ACTCOL_26") (pintype "output"))
    )
    (net (code "26") (name "Net-(U6-LED_LINK)") (class "Default")
      (node (ref "R10") (pin "1") (pinfunction "1_1") (pintype "passive"))
      (node (ref "RS4") (pin "2") (pinfunction "2_2") (pintype "passive"))
      (node (ref "U6") (pin "28") (pinfunction "LED_LINK_28") (pintype "output"))
    )
    (net (code "27") (name "Net-(U6-PFBIN1)") (class "Default")
      (node (ref "C15") (pin "2") (pinfunction "2_2") (pintype "passive"))
      (node (ref "C16") (pin "2") (pinfunction "2_2") (pintype "passive"))
      (node (ref "C17") (pin "2") (pinfunction "2_2") (pintype "passive"))
      (node (ref "C18") (pin "2") (pinfunction "2_2") (pintype "passive"))
      (node (ref "U6") (pin "18") (pinfunction "PFBIN1_18") (pintype "input"))
      (node (ref "U6") (pin "23") (pinfunction "PFBOUT_23") (pintype "output"))
      (node (ref "U6") (pin "37") (pinfunction "PFBIN2_37") (pintype "input"))
    )
    (net (code "28") (name "Net-(U6-RBIAS)") (class "Default")
      (node (ref "R6") (pin "2") (pinfunction "2_2") (pintype "passive"))
      (node (ref "U6") (pin "24") (pinfunction "RBIAS_24") (pintype "bidirectional"))
    )
    (net (code "29") (name "Net-(U6-RESERVED)") (class "Default")
      (node (ref "R8") (pin "1") (pinfunction "1_1") (pintype "passive"))
      (node (ref "U6") (pin "20") (pinfunction "RESERVED_20") (pintype "input"))
    )
    (net (code "30") (name "Net-(U6-RESERVED_)") (class "Default")
      (node (ref "R7") (pin "1") (pinfunction "1_1") (pintype "passive"))
      (node (ref "U6") (pin "21") (pinfunction "RESERVED__21") (pintype "input"))
    )
    (net (code "31") (name "Net-(U6-RX_DV)") (class "Default")
      (node (ref "RS1") (pin "2") (pinfunction "2_2") (pintype "passive"))
      (node (ref "U6") (pin "39") (pinfunction "RX_DV_39") (pintype "output"))
    )
    (net (code "32") (name "Net-(U6-TCK)") (class "Default")
      (node (ref "JP8") (pin "3") (pinfunction "3_3") (pintype "passive"))
      (node (ref "U6") (pin "8") (pinfunction "TCK_8") (pintype "input"))
    )
    (net (code "33") (name "Net-(U6-TDI)") (class "Default")
      (node (ref "JP8") (pin "1") (pinfunction "1_1") (pintype "passive"))
      (node (ref "U6") (pin "12") (pinfunction "TDI_12") (pintype "input"))
    )
    (net (code "34") (name "Net-(U6-TDO)") (class "Default")
      (node (ref "JP8") (pin "2") (pinfunction "2_2") (pintype "passive"))
      (node (ref "U6") (pin "9") (pinfunction "TDO_9") (pintype "output"))
    )
    (net (code "35") (name "Net-(U6-TMS)") (class "Default")
      (node (ref "JP8") (pin "4") (pinfunction "4_4") (pintype "passive"))
      (node (ref "U6") (pin "10") (pinfunction "TMS_10") (pintype "input"))
    )
    (net (code "36") (name "Net-(U6-~{RESET})") (class "Default")
      (node (ref "C23") (pin "1") (pinfunction "1_1") (pintype "passive"))
      (node (ref "R11") (pin "1") (pinfunction "1_1") (pintype "passive"))
      (node (ref "U6") (pin "29") (pinfunction "~{RESET}_29") (pintype "input"))
    )
    (net (code "37") (name "Net-(U6-~{TRST})") (class "Default")
      (node (ref "JP8") (pin "5") (pinfunction "5_5") (pintype "passive"))
      (node (ref "U6") (pin "11") (pinfunction "~{TRST}_11") (pintype "input"))
    )
    (net (code "38") (name "Net-(U7-ILIM)") (class "Default")
      (node (ref "R13") (pin "2") (pinfunction "2_2") (pintype "passive"))
      (node (ref "U7") (pin "5") (pinfunction "ILIM_5") (pintype "passive"))
    )
    (net (code "39") (name "Net-(U10-SW)") (class "Default")
      (node (ref "L1") (pin "1") (pinfunction "1_1") (pintype "passive"))
      (node (ref "U10") (pin "3") (pinfunction "SW_3") (pintype "passive"))
    )
    (net (code "40") (name "Net-(U10-VFB)") (class "Default")
      (node (ref "C24") (pin "2") (pinfunction "2_2") (pintype "passive"))
      (node (ref "R14") (pin "1") (pinfunction "1_1") (pintype "passive"))
      (node (ref "R15") (pin "2") (pinfunction "2_2") (pintype "passive"))
      (node (ref "U10") (pin "5") (pinfunction "VFB_5") (pintype "input"))
    )
    (net (code "41") (name "Net-(U13A-D)") (class "Default")
      (node (ref "C28") (pin "2") (pinfunction "2_2") (pintype "passive"))
      (node (ref "TP7") (pin "TP") (pinfunction "TP_TP") (pintype "input"))
      (node (ref "U13") (pin "43") (pinfunction "D_43") (pintype "bidirectional"))
      (node (ref "U5") (pin "28") (pinfunction "D_28") (pintype "bidirectional"))
    )
    (net (code "42") (name "Net-(U13A-S1)") (class "Default")
      (node (ref "JP11") (pin "1") (pinfunction "1_1") (pintype "passive"))
      (node (ref "U13") (pin "12") (pinfunction "S1_12") (pintype "bidirectional"))
    )
    (net (code "43") (name "Net-(U13A-S2)") (class "Default")
      (node (ref "JP11") (pin "2") (pinfunction "2_2") (pintype "passive"))
      (node (ref "U13") (pin "11") (pinfunction "S2_11") (pintype "bidirectional"))
    )
    (net (code "44") (name "Net-(U13A-S3)") (class "Default")
      (node (ref "JP11") (pin "3") (pinfunction "3_3") (pintype "passive"))
      (node (ref "U13") (pin "10") (pinfunction "S3_10") (pintype "bidirectional"))
    )
    (net (code "45") (name "Net-(U13A-S4)") (class "Default")
      (node (ref "JP11") (pin "4") (pinfunction "4_4") (pintype "passive"))
      (node (ref "U13") (pin "9") (pinfunction "S4_9") (pintype "bidirectional"))
    )
    (net (code "46") (name "Net-(U13A-S5)") (class "Default")
      (node (ref "JP11") (pin "5") (pinfunction "5_5") (pintype "passive"))
      (node (ref "U13") (pin "8") (pinfunction "S5_8") (pintype "bidirectional"))
    )
    (net (code "47") (name "Net-(U13A-S6)") (class "Default")
      (node (ref "JP11") (pin "6") (pinfunction "6_6") (pintype "passive"))
      (node (ref "U13") (pin "7") (pinfunction "S6_7") (pintype "bidirectional"))
    )
    (net (code "48") (name "Net-(U13A-S7)") (class "Default")
      (node (ref "JP11") (pin "7") (pinfunction "7_7") (pintype "passive"))
      (node (ref "U13") (pin "6") (pinfunction "S7_6") (pintype "bidirectional"))
    )
    (net (code "49") (name "Net-(U13A-S8)") (class "Default")
      (node (ref "JP11") (pin "8") (pinfunction "8_8") (pintype "passive"))
      (node (ref "U13") (pin "5") (pinfunction "S8_5") (pintype "bidirectional"))
    )
    (net (code "50") (name "Net-(U13A-S9)") (class "Default")
      (node (ref "JP11") (pin "9") (pinfunction "9_9") (pintype "passive"))
      (node (ref "U13") (pin "4") (pinfunction "S9_4") (pintype "bidirectional"))
    )
    (net (code "51") (name "Net-(U13A-S10)") (class "Default")
      (node (ref "JP11") (pin "10") (pinfunction "10_10") (pintype "passive"))
      (node (ref "U13") (pin "3") (pinfunction "S10_3") (pintype "bidirectional"))
    )
    (net (code "52") (name "Net-(U13A-S11)") (class "Default")
      (node (ref "JP15") (pin "1") (pinfunction "1_1") (pintype "passive"))
      (node (ref "U13") (pin "2") (pinfunction "S11_2") (pintype "bidirectional"))
    )
    (net (code "53") (name "Net-(U13A-S12)") (class "Default")
      (node (ref "JP15") (pin "2") (pinfunction "2_2") (pintype "passive"))
      (node (ref "U13") (pin "1") (pinfunction "S12_1") (pintype "bidirectional"))
    )
    (net (code "54") (name "Net-(U13A-S13)") (class "Default")
      (node (ref "JP15") (pin "3") (pinfunction "3_3") (pintype "passive"))
      (node (ref "U13") (pin "48") (pinfunction "S13_48") (pintype "bidirectional"))
    )
    (net (code "55") (name "Net-(U13A-S14)") (class "Default")
      (node (ref "JP15") (pin "4") (pinfunction "4_4") (pintype "passive"))
      (node (ref "U13") (pin "47") (pinfunction "S14_47") (pintype "bidirectional"))
    )
    (net (code "56") (name "Net-(U13A-S15)") (class "Default")
      (node (ref "JP15") (pin "5") (pinfunction "5_5") (pintype "passive"))
      (node (ref "U13") (pin "46") (pinfunction "S15_46") (pintype "bidirectional"))
    )
    (net (code "57") (name "Net-(U13A-S16)") (class "Default")
      (node (ref "JP15") (pin "6") (pinfunction "6_6") (pintype "passive"))
      (node (ref "U13") (pin "45") (pinfunction "S16_45") (pintype "bidirectional"))
    )
    (net (code "58") (name "Net-(U13B-D)") (class "Default")
      (node (ref "C27") (pin "1") (pinfunction "1_1") (pintype "passive"))
      (node (ref "C31") (pin "2") (pinfunction "2_2") (pintype "passive"))
      (node (ref "TP8") (pin "TP") (pinfunction "TP_TP") (pintype "input"))
      (node (ref "U13") (pin "41") (pinfunction "D_41") (pintype "bidirectional"))
      (node (ref "U3") (pin "6") (pinfunction "IN-_6") (pintype "input"))
    )
    (net (code "59") (name "Net-(U13B-S1)") (class "Default")
      (node (ref "JP12") (pin "1") (pinfunction "1_1") (pintype "passive"))
      (node (ref "U13") (pin "25") (pinfunction "S1_25") (pintype "bidirectional"))
    )
    (net (code "60") (name "Net-(U13B-S2)") (class "Default")
      (node (ref "JP12") (pin "2") (pinfunction "2_2") (pintype "passive"))
      (node (ref "U13") (pin "26") (pinfunction "S2_26") (pintype "bidirectional"))
    )
    (net (code "61") (name "Net-(U13B-S3)") (class "Default")
      (node (ref "JP12") (pin "3") (pinfunction "3_3") (pintype "passive"))
      (node (ref "U13") (pin "27") (pinfunction "S3_27") (pintype "bidirectional"))
    )
    (net (code "62") (name "Net-(U13B-S4)") (class "Default")
      (node (ref "JP12") (pin "4") (pinfunction "4_4") (pintype "passive"))
      (node (ref "U13") (pin "28") (pinfunction "S4_28") (pintype "bidirectional"))
    )
    (net (code "63") (name "Net-(U13B-S5)") (class "Default")
      (node (ref "JP12") (pin "5") (pinfunction "5_5") (pintype "passive"))
      (node (ref "U13") (pin "29") (pinfunction "S5_29") (pintype "bidirectional"))
    )
    (net (code "64") (name "Net-(U13B-S6)") (class "Default")
      (node (ref "JP12") (pin "6") (pinfunction "6_6") (pintype "passive"))
      (node (ref "U13") (pin "30") (pinfunction "S6_30") (pintype "bidirectional"))
    )
    (net (code "65") (name "Net-(U13B-S7)") (class "Default")
      (node (ref "JP12") (pin "7") (pinfunction "7_7") (pintype "passive"))
      (node (ref "U13") (pin "31") (pinfunction "S7_31") (pintype "bidirectional"))
    )
    (net (code "66") (name "Net-(U13B-S8)") (class "Default")
      (node (ref "JP12") (pin "8") (pinfunction "8_8") (pintype "passive"))
      (node (ref "U13") (pin "32") (pinfunction "S8_32") (pintype "bidirectional"))
    )
    (net (code "67") (name "Net-(U13B-S9)") (class "Default")
      (node (ref "JP12") (pin "9") (pinfunction "9_9") (pintype "passive"))
      (node (ref "U13") (pin "33") (pinfunction "S9_33") (pintype "bidirectional"))
    )
    (net (code "68") (name "Net-(U13B-S10)") (class "Default")
      (node (ref "JP12") (pin "10") (pinfunction "10_10") (pintype "passive"))
      (node (ref "U13") (pin "34") (pinfunction "S10_34") (pintype "bidirectional"))
    )
    (net (code "69") (name "Net-(U13B-S11)") (class "Default")
      (node (ref "JP16") (pin "1") (pinfunction "1_1") (pintype "passive"))
      (node (ref "U13") (pin "35") (pinfunction "S11_35") (pintype "bidirectional"))
    )
    (net (code "70") (name "Net-(U13B-S12)") (class "Default")
      (node (ref "JP16") (pin "2") (pinfunction "2_2") (pintype "passive"))
      (node (ref "U13") (pin "36") (pinfunction "S12_36") (pintype "bidirectional"))
    )
    (net (code "71") (name "Net-(U13B-S13)") (class "Default")
      (node (ref "JP16") (pin "3") (pinfunction "3_3") (pintype "passive"))
      (node (ref "U13") (pin "37") (pinfunction "S13_37") (pintype "bidirectional"))
    )
    (net (code "72") (name "Net-(U13B-S14)") (class "Default")
      (node (ref "JP16") (pin "4") (pinfunction "4_4") (pintype "passive"))
      (node (ref "U13") (pin "38") (pinfunction "S14_38") (pintype "bidirectional"))
    )
    (net (code "73") (name "Net-(U13B-S15)") (class "Default")
      (node (ref "JP16") (pin "5") (pinfunction "5_5") (pintype "passive"))
      (node (ref "U13") (pin "39") (pinfunction "S15_39") (pintype "bidirectional"))
    )
    (net (code "74") (name "Net-(U13B-S16)") (class "Default")
      (node (ref "JP16") (pin "6") (pinfunction "6_6") (pintype "passive"))
      (node (ref "U13") (pin "40") (pinfunction "S16_40") (pintype "bidirectional"))
    )
    (net (code "75") (name "Net-(U14A-D)") (class "Default")
      (node (ref "C20") (pin "2") (pinfunction "2_2") (pintype "passive"))
      (node (ref "C29") (pin "1") (pinfunction "1_1") (pintype "passive"))
      (node (ref "TP5") (pin "TP") (pinfunction "TP_TP") (pintype "input"))
      (node (ref "U14") (pin "43") (pinfunction "D_43") (pintype "bidirectional"))
      (node (ref "U3") (pin "1") (pinfunction "OUT_1") (pintype "output"))
    )
    (net (code "76") (name "Net-(U14A-S1)") (class "Default")
      (node (ref "JP5") (pin "1") (pinfunction "1_1") (pintype "passive"))
      (node (ref "U14") (pin "12") (pinfunction "S1_12") (pintype "bidirectional"))
    )
    (net (code "77") (name "Net-(U14A-S2)") (class "Default")
      (node (ref "JP5") (pin "2") (pinfunction "2_2") (pintype "passive"))
      (node (ref "U14") (pin "11") (pinfunction "S2_11") (pintype "bidirectional"))
    )
    (net (code "78") (name "Net-(U14A-S3)") (class "Default")
      (node (ref "JP5") (pin "3") (pinfunction "3_3") (pintype "passive"))
      (node (ref "U14") (pin "10") (pinfunction "S3_10") (pintype "bidirectional"))
    )
    (net (code "79") (name "Net-(U14A-S4)") (class "Default")
      (node (ref "JP5") (pin "4") (pinfunction "4_4") (pintype "passive"))
      (node (ref "U14") (pin "9") (pinfunction "S4_9") (pintype "bidirectional"))
    )
    (net (code "80") (name "Net-(U14A-S5)") (class "Default")
      (node (ref "JP5") (pin "5") (pinfunction "5_5") (pintype "passive"))
      (node (ref "U14") (pin "8") (pinfunction "S5_8") (pintype "bidirectional"))
    )
    (net (code "81") (name "Net-(U14A-S6)") (class "Default")
      (node (ref "JP5") (pin "6") (pinfunction "6_6") (pintype "passive"))
      (node (ref "U14") (pin "7") (pinfunction "S6_7") (pintype "bidirectional"))
    )
    (net (code "82") (name "Net-(U14A-S7)") (class "Default")
      (node (ref "JP5") (pin "7") (pinfunction "7_7") (pintype "passive"))
      (node (ref "U14") (pin "6") (pinfunction "S7_6") (pintype "bidirectional"))
    )
    (net (code "83") (name "Net-(U14A-S8)") (class "Default")
      (node (ref "JP5") (pin "8") (pinfunction "8_8") (pintype "passive"))
      (node (ref "U14") (pin "5") (pinfunction "S8_5") (pintype "bidirectional"))
    )
    (net (code "84") (name "Net-(U14A-S9)") (class "Default")
      (node (ref "JP5") (pin "9") (pinfunction "9_9") (pintype "passive"))
      (node (ref "U14") (pin "4") (pinfunction "S9_4") (pintype "bidirectional"))
    )
    (net (code "85") (name "Net-(U14A-S10)") (class "Default")
      (node (ref "JP5") (pin "10") (pinfunction "10_10") (pintype "passive"))
      (node (ref "U14") (pin "3") (pinfunction "S10_3") (pintype "bidirectional"))
    )
    (net (code "86") (name "Net-(U14A-S11)") (class "Default")
      (node (ref "JP13") (pin "1") (pinfunction "1_1") (pintype "passive"))
      (node (ref "U14") (pin "2") (pinfunction "S11_2") (pintype "bidirectional"))
    )
    (net (code "87") (name "Net-(U14A-S12)") (class "Default")
      (node (ref "JP13") (pin "2") (pinfunction "2_2") (pintype "passive"))
      (node (ref "U14") (pin "1") (pinfunction "S12_1") (pintype "bidirectional"))
    )
    (net (code "88") (name "Net-(U14A-S13)") (class "Default")
      (node (ref "JP13") (pin "3") (pinfunction "3_3") (pintype "passive"))
      (node (ref "U14") (pin "48") (pinfunction "S13_48") (pintype "bidirectional"))
    )
    (net (code "89") (name "Net-(U14A-S14)") (class "Default")
      (node (ref "JP13") (pin "4") (pinfunction "4_4") (pintype "passive"))
      (node (ref "U14") (pin "47") (pinfunction "S14_47") (pintype "bidirectional"))
    )
    (net (code "90") (name "Net-(U14A-S15)") (class "Default")
      (node (ref "JP13") (pin "5") (pinfunction "5_5") (pintype "passive"))
      (node (ref "U14") (pin "46") (pinfunction "S15_46") (pintype "bidirectional"))
    )
    (net (code "91") (name "Net-(U14A-S16)") (class "Default")
      (node (ref "JP13") (pin "6") (pinfunction "6_6") (pintype "passive"))
      (node (ref "U14") (pin "45") (pinfunction "S16_45") (pintype "bidirectional"))
    )
    (net (code "92") (name "Net-(U14B-D)") (class "Default")
      (node (ref "C30") (pin "2") (pinfunction "2_2") (pintype "passive"))
      (node (ref "C32") (pin "2") (pinfunction "2_2") (pintype "passive"))
      (node (ref "TP6") (pin "TP") (pinfunction "TP_TP") (pintype "input"))
      (node (ref "U14") (pin "41") (pinfunction "D_41") (pintype "bidirectional"))
      (node (ref "U2") (pin "8") (pinfunction "D_8") (pintype "bidirectional"))
    )
    (net (code "93") (name "Net-(U14B-S1)") (class "Default")
      (node (ref "JP6") (pin "1") (pinfunction "1_1") (pintype "passive"))
      (node (ref "U14") (pin "25") (pinfunction "S1_25") (pintype "bidirectional"))
    )
    (net (code "94") (name "Net-(U14B-S2)") (class "Default")
      (node (ref "JP6") (pin "2") (pinfunction "2_2") (pintype "passive"))
      (node (ref "U14") (pin "26") (pinfunction "S2_26") (pintype "bidirectional"))
    )
    (net (code "95") (name "Net-(U14B-S3)") (class "Default")
      (node (ref "JP6") (pin "3") (pinfunction "3_3") (pintype "passive"))
      (node (ref "U14") (pin "27") (pinfunction "S3_27") (pintype "bidirectional"))
    )
    (net (code "96") (name "Net-(U14B-S4)") (class "Default")
      (node (ref "JP6") (pin "4") (pinfunction "4_4") (pintype "passive"))
      (node (ref "U14") (pin "28") (pinfunction "S4_28") (pintype "bidirectional"))
    )
    (net (code "97") (name "Net-(U14B-S5)") (class "Default")
      (node (ref "JP6") (pin "5") (pinfunction "5_5") (pintype "passive"))
      (node (ref "U14") (pin "29") (pinfunction "S5_29") (pintype "bidirectional"))
    )
    (net (code "98") (name "Net-(U14B-S6)") (class "Default")
      (node (ref "JP6") (pin "6") (pinfunction "6_6") (pintype "passive"))
      (node (ref "U14") (pin "30") (pinfunction "S6_30") (pintype "bidirectional"))
    )
    (net (code "99") (name "Net-(U14B-S7)") (class "Default")
      (node (ref "JP6") (pin "7") (pinfunction "7_7") (pintype "passive"))
      (node (ref "U14") (pin "31") (pinfunction "S7_31") (pintype "bidirectional"))
    )
    (net (code "100") (name "Net-(U14B-S8)") (class "Default")
      (node (ref "JP6") (pin "8") (pinfunction "8_8") (pintype "passive"))
      (node (ref "U14") (pin "32") (pinfunction "S8_32") (pintype "bidirectional"))
    )
    (net (code "101") (name "Net-(U14B-S9)") (class "Default")
      (node (ref "JP6") (pin "9") (pinfunction "9_9") (pintype "passive"))
      (node (ref "U14") (pin "33") (pinfunction "S9_33") (pintype "bidirectional"))
    )
    (net (code "102") (name "Net-(U14B-S10)") (class "Default")
      (node (ref "JP6") (pin "10") (pinfunction "10_10") (pintype "passive"))
      (node (ref "U14") (pin "34") (pinfunction "S10_34") (pintype "bidirectional"))
    )
    (net (code "103") (name "Net-(U14B-S11)") (class "Default")
      (node (ref "JP14") (pin "1") (pinfunction "1_1") (pintype "passive"))
      (node (ref "U14") (pin "35") (pinfunction "S11_35") (pintype "bidirectional"))
    )
    (net (code "104") (name "Net-(U14B-S12)") (class "Default")
      (node (ref "JP14") (pin "2") (pinfunction "2_2") (pintype "passive"))
      (node (ref "U14") (pin "36") (pinfunction "S12_36") (pintype "bidirectional"))
    )
    (net (code "105") (name "Net-(U14B-S13)") (class "Default")
      (node (ref "JP14") (pin "3") (pinfunction "3_3") (pintype "passive"))
      (node (ref "U14") (pin "37") (pinfunction "S13_37") (pintype "bidirectional"))
    )
    (net (code "106") (name "Net-(U14B-S14)") (class "Default")
      (node (ref "JP14") (pin "4") (pinfunction "4_4") (pintype "passive"))
      (node (ref "U14") (pin "38") (pinfunction "S14_38") (pintype "bidirectional"))
    )
    (net (code "107") (name "Net-(U14B-S15)") (class "Default")
      (node (ref "JP14") (pin "5") (pinfunction "5_5") (pintype "passive"))
      (node (ref "U14") (pin "39") (pinfunction "S15_39") (pintype "bidirectional"))
    )
    (net (code "108") (name "Net-(U14B-S16)") (class "Default")
      (node (ref "JP14") (pin "6") (pinfunction "6_6") (pintype "passive"))
      (node (ref "U14") (pin "40") (pinfunction "S16_40") (pintype "bidirectional"))
    )
    (net (code "109") (name "Net-(U15-D)") (class "Default")
      (node (ref "C25") (pin "1") (pinfunction "1_1") (pintype "passive"))
      (node (ref "U15") (pin "5") (pinfunction "D_5") (pintype "bidirectional"))
    )
    (net (code "110") (name "Net-(U15-S1)") (class "Default")
      (node (ref "R20") (pin "1") (pinfunction "1_1") (pintype "passive"))
      (node (ref "U15") (pin "4") (pinfunction "S1_4") (pintype "bidirectional"))
    )
    (net (code "111") (name "Net-(U15-S2)") (class "Default")
      (node (ref "RA") (pin "2") (pinfunction "2_2") (pintype "passive"))
      (node (ref "TP10") (pin "TP") (pinfunction "TP_TP") (pintype "input"))
      (node (ref "U15") (pin "6") (pinfunction "S2_6") (pintype "bidirectional"))
    )
    (net (code "112") (name "PA0") (class "Default")
      (node (ref "JP1") (pin "12") (pinfunction "12_12") (pintype "passive"))
      (node (ref "S1") (pin "1") (pinfunction "0_1") (pintype "passive"))
      (node (ref "S1") (pin "2") (pinfunction "0_2") (pintype "passive"))
    )
    (net (code "113") (name "PA2") (class "Default")
      (node (ref "JP1") (pin "14") (pinfunction "14_14") (pintype "passive"))
      (node (ref "R5") (pin "1") (pinfunction "1_1") (pintype "passive"))
      (node (ref "U6") (pin "30") (pinfunction "MDIO_30") (pintype "bidirectional"))
    )
    (net (code "114") (name "PA7") (class "Default")
      (node (ref "JP1") (pin "17") (pinfunction "17_17") (pintype "passive"))
      (node (ref "RS2") (pin "1") (pinfunction "1_1") (pintype "passive"))
      (node (ref "U6") (pin "40") (pinfunction "CRS_DV_40") (pintype "output"))
    )
    (net (code "115") (name "PA9") (class "Default")
      (node (ref "JP10") (pin "1") (pinfunction "1_1") (pintype "passive"))
      (node (ref "JP2") (pin "44") (pinfunction "44_44") (pintype "passive"))
      (node (ref "R22") (pin "2") (pinfunction "2_2") (pintype "passive"))
    )
    (net (code "116") (name "PB4") (class "Default")
      (node (ref "JP2") (pin "25") (pinfunction "25_25") (pintype "passive"))
      (node (ref "U5") (pin "16") (pinfunction "A1_16") (pintype "input"))
    )
    (net (code "117") (name "PB5") (class "Default")
      (node (ref "JP2") (pin "26") (pinfunction "26_26") (pintype "passive"))
      (node (ref "U5") (pin "15") (pinfunction "A2_15") (pintype "input"))
    )
    (net (code "118") (name "PB6") (class "Default")
      (node (ref "JP2") (pin "23") (pinfunction "23_23") (pintype "passive"))
      (node (ref "JP7") (pin "3") (pinfunction "3_3") (pintype "passive"))
      (node (ref "R12") (pin "1") (pinfunction "1_1") (pintype "passive"))
      (node (ref "U1") (pin "16") (pinfunction "SCL_16") (pintype "bidirectional"))
      (node (ref "U4") (pin "6") (pinfunction "SCL_6") (pintype "input"))
    )
    (net (code "119") (name "PB7") (class "Default")
      (node (ref "JP2") (pin "24") (pinfunction "24_24") (pintype "passive"))
      (node (ref "U5") (pin "17") (pinfunction "A0_17") (pintype "input"))
    )
    (net (code "120") (name "PB8") (class "Default")
      (node (ref "JP2") (pin "19") (pinfunction "19_19") (pintype "passive"))
      (node (ref "U1") (pin "8") (pinfunction "MCLK_8") (pintype "bidirectional"))
    )
    (net (code "121") (name "PB9") (class "Default")
      (node (ref "JP2") (pin "20") (pinfunction "20_20") (pintype "passive"))
      (node (ref "JP7") (pin "2") (pinfunction "2_2") (pintype "passive"))
      (node (ref "R21") (pin "1") (pinfunction "1_1") (pintype "passive"))
      (node (ref "U1") (pin "15") (pinfunction "SDA_15") (pintype "bidirectional"))
      (node (ref "U4") (pin "5") (pinfunction "SDA_5") (pintype "open_collector"))
    )
    (net (code "122") (name "PB11") (class "Default")
      (node (ref "JP1") (pin "35") (pinfunction "35_35") (pintype "passive"))
      (node (ref "U6") (pin "2") (pinfunction "TX_EN_2") (pintype "input"))
    )
    (net (code "123") (name "PB12") (class "Default")
      (node (ref "JP1") (pin "36") (pinfunction "36_36") (pintype "passive"))
      (node (ref "U6") (pin "3") (pinfunction "TXD_0_3") (pintype "input"))
    )
    (net (code "124") (name "PB13") (class "Default")
      (node (ref "JP1") (pin "37") (pinfunction "37_37") (pintype "passive"))
      (node (ref "U6") (pin "4") (pinfunction "TXD_1_4") (pintype "input"))
    )
    (net (code "125") (name "PC1") (class "Default")
      (node (ref "JP1") (pin "7") (pinfunction "7_7") (pintype "passive"))
      (node (ref "U6") (pin "31") (pinfunction "MDC_31") (pintype "input"))
    )
    (net (code "126") (name "PC2") (class "Default")
      (node (ref "JP1") (pin "10") (pinfunction "10_10") (pintype "passive"))
      (node (ref "SJ3") (pin "1") (pinfunction "1_1") (pintype "passive"))
    )
    (net (code "127") (name "PC4") (class "Default")
      (node (ref "JP1") (pin "20") (pinfunction "20_20") (pintype "passive"))
      (node (ref "U6") (pin "43") (pinfunction "RXD_0_43") (pintype "output"))
    )
    (net (code "128") (name "PC5") (class "Default")
      (node (ref "JP1") (pin "19") (pinfunction "19_19") (pintype "passive"))
      (node (ref "U6") (pin "44") (pinfunction "RXD_1_44") (pintype "output"))
    )
    (net (code "129") (name "PC9") (class "Default")
      (node (ref "JP2") (pin "46") (pinfunction "46_46") (pintype "passive"))
      (node (ref "SJ2") (pin "2") (pinfunction "2_2") (pintype "passive"))
    )
    (net (code "130") (name "PC10") (class "Default")
      (node (ref "JP2") (pin "37") (pinfunction "37_37") (pintype "passive"))
      (node (ref "U11") (pin "6") (pinfunction "SCK_6") (pintype "input"))
      (node (ref "U13") (pin "19") (pinfunction "SCLK_19") (pintype "input"))
      (node (ref "U14") (pin "19") (pinfunction "SCLK_19") (pintype "input"))
      (node (ref "U8") (pin "6") (pinfunction "SCK_6") (pintype "input"))
      (node (ref "U9") (pin "6") (pinfunction "SCK_6") (pintype "input"))
    )
    (net (code "131") (name "PC11") (class "Default")
      (node (ref "JP2") (pin "38") (pinfunction "38_38") (pintype "passive"))
      (node (ref "U11") (pin "2") (pinfunction "SO_2") (pintype "tri_state"))
      (node (ref "U8") (pin "2") (pinfunction "SO_2") (pintype "tri_state"))
      (node (ref "U9") (pin "2") (pinfunction "SO_2") (pintype "tri_state"))
    )
    (net (code "132") (name "PC12") (class "Default")
      (node (ref "JP2") (pin "35") (pinfunction "35_35") (pintype "passive"))
      (node (ref "U11") (pin "5") (pinfunction "SI_5") (pintype "input"))
      (node (ref "U13") (pin "18") (pinfunction "DIN_18") (pintype "input"))
      (node (ref "U14") (pin "18") (pinfunction "DIN_18") (pintype "input"))
      (node (ref "U8") (pin "5") (pinfunction "SI_5") (pintype "input"))
      (node (ref "U9") (pin "5") (pinfunction "SI_5") (pintype "input"))
    )
    (net (code "133") (name "PD0") (class "Default")
      (node (ref "JP2") (pin "36") (pinfunction "36_36") (pintype "passive"))
      (node (ref "U8") (pin "1") (pinfunction "~{CS}_1") (pintype "input"))
      (node (ref "U9") (pin "1") (pinfunction "~{CS}_1") (pintype "input"))
    )
    (net (code "134") (name "PD1") (class "Default")
      (node (ref "JP2") (pin "33") (pinfunction "33_33") (pintype "passive"))
      (node (ref "U11") (pin "1") (pinfunction "~{CS}_1") (pintype "input"))
    )
    (net (code "135") (name "PD2") (class "Default")
      (node (ref "JP2") (pin "34") (pinfunction "34_34") (pintype "passive"))
      (node (ref "U13") (pin "17") (pinfunction "~{SYNC}_17") (pintype "input"))
      (node (ref "U14") (pin "17") (pinfunction "~{SYNC}_17") (pintype "input"))
    )
    (net (code "136") (name "PD8") (class "Default")
      (node (ref "JP1") (pin "40") (pinfunction "40_40") (pintype "passive"))
      (node (ref "U7") (pin "3") (pinfunction "EN_3") (pintype "input"))
    )
    (net (code "137") (name "PD9") (class "Default")
      (node (ref "JP1") (pin "41") (pinfunction "41_41") (pintype "passive"))
      (node (ref "U7") (pin "4") (pinfunction "~{FAULT}_4") (pintype "output"))
    )
    (net (code "138") (name "PE2") (class "Default")
      (node (ref "J3") (pin "3") (pinfunction "2_3") (pintype "passive"))
      (node (ref "JP2") (pin "15") (pinfunction "15_15") (pintype "passive"))
    )
    (net (code "139") (name "PE4") (class "Default")
      (node (ref "JP2") (pin "13") (pinfunction "13_13") (pintype "passive"))
      (node (ref "U15") (pin "1") (pinfunction "IN_1") (pintype "input"))
    )
    (net (code "140") (name "PE5") (class "Default")
      (node (ref "JP2") (pin "14") (pinfunction "14_14") (pintype "passive"))
      (node (ref "U2") (pin "1") (pinfunction "A0_1") (pintype "input"))
    )
    (net (code "141") (name "PE6") (class "Default")
      (node (ref "JP2") (pin "11") (pinfunction "11_11") (pintype "passive"))
      (node (ref "U2") (pin "10") (pinfunction "A1_10") (pintype "input"))
    )
    (net (code "142") (name "RD_N") (class "Default")
      (node (ref "J2") (pin "6") (pinfunction "RD-_6") (pintype "passive"))
      (node (ref "R4") (pin "1") (pinfunction "1_1") (pintype "passive"))
      (node (ref "U6") (pin "13") (pinfunction "RD-_13") (pintype "bidirectional"))
    )
    (net (code "143") (name "RD_P") (class "Default")
      (node (ref "J2") (pin "4") (pinfunction "RD+_4") (pintype "passive"))
      (node (ref "R3") (pin "1") (pinfunction "1_1") (pintype "passive"))
      (node (ref "U6") (pin "14") (pinfunction "RD+_14") (pintype "bidirectional"))
    )
    (net (code "144") (name "RFB") (class "Default")
      (node (ref "R19") (pin "1") (pinfunction "1_1") (pintype "passive"))
      (node (ref "U1") (pin "4") (pinfunction "RFB_4") (pintype "bidirectional"))
    )
    (net (code "145") (name "TD_N") (class "Default")
      (node (ref "J2") (pin "3") (pinfunction "TD-_3") (pintype "passive"))
      (node (ref "R2") (pin "1") (pinfunction "1_1") (pintype "passive"))
      (node (ref "U6") (pin "16") (pinfunction "TD-_16") (pintype "bidirectional"))
    )
    (net (code "146") (name "TD_P") (class "Default")
      (node (ref "J2") (pin "1") (pinfunction "TD+_1") (pintype "passive"))
      (node (ref "R1") (pin "1") (pinfunction "1_1") (pintype "passive"))
      (node (ref "U6") (pin "17") (pinfunction "TD+_17") (pintype "bidirectional"))
    )
    (net (code "147") (name "USB_N") (class "Default")
      (node (ref "J1") (pin "2") (pinfunction "D-_2") (pintype "passive"))
      (node (ref "JP1") (pin "38") (pinfunction "38_38") (pintype "passive"))
    )
    (net (code "148") (name "USB_P") (class "Default")
      (node (ref "J1") (pin "3") (pinfunction "D+_3") (pintype "passive"))
      (node (ref "JP1") (pin "39") (pinfunction "39_39") (pintype "passive"))
    )
    (net (code "149") (name "VCC") (class "Default")
      (node (ref "C10") (pin "1") (pinfunction "1_1") (pintype "passive"))
      (node (ref "C11") (pin "1") (pinfunction "1_1") (pintype "passive"))
      (node (ref "C12") (pin "1") (pinfunction "1_1") (pintype "passive"))
      (node (ref "C13") (pin "2") (pinfunction "2_2") (pintype "passive"))
      (node (ref "C14") (pin "1") (pinfunction "1_1") (pintype "passive"))
      (node (ref "C22") (pin "1") (pinfunction "1_1") (pintype "passive"))
      (node (ref "C3") (pin "1") (pinfunction "1_1") (pintype "passive"))
      (node (ref "C4") (pin "1") (pinfunction "1_1") (pintype "passive"))
      (node (ref "C5") (pin "1") (pinfunction "1_1") (pintype "passive"))
      (node (ref "C6") (pin "1") (pinfunction "1_1") (pintype "passive"))
      (node (ref "C7") (pin "1") (pinfunction "1_1") (pintype "passive"))
      (node (ref "C8") (pin "1") (pinfunction "1_1") (pintype "passive"))
      (node (ref "C9") (pin "1") (pinfunction "1_1") (pintype "passive"))
      (node (ref "J2") (pin "2") (pinfunction "TCT_2") (pintype "passive"))
      (node (ref "J2") (pin "5") (pinfunction "RCT_5") (pintype "passive"))
      (node (ref "J2") (pin "AG") (pinfunction "AG_AG") (pintype "passive"))
      (node (ref "J2") (pin "AY") (pinfunction "AY_AY") (pintype "passive"))
      (node (ref "JP4") (pin "1") (pinfunction "1_1") (pintype "passive"))
      (node (ref "R1") (pin "2") (pinfunction "2_2") (pintype "passive"))
      (node (ref "R11") (pin "2") (pinfunction "2_2") (pintype "passive"))
      (node (ref "R12") (pin "2") (pinfunction "2_2") (pintype "passive"))
      (node (ref "R16") (pin "2") (pinfunction "2_2") (pintype "passive"))
      (node (ref "R2") (pin "2") (pinfunction "2_2") (pintype "passive"))
      (node (ref "R21") (pin "2") (pinfunction "2_2") (pintype "passive"))
      (node (ref "R3") (pin "2") (pinfunction "2_2") (pintype "passive"))
      (node (ref "R4") (pin "2") (pinfunction "2_2") (pintype "passive"))
      (node (ref "R5") (pin "2") (pinfunction "2_2") (pintype "passive"))
      (node (ref "R7") (pin "2") (pinfunction "2_2") (pintype "passive"))
      (node (ref "R8") (pin "2") (pinfunction "2_2") (pintype "passive"))
      (node (ref "RS1") (pin "1") (pinfunction "1_1") (pintype "passive"))
      (node (ref "RS3") (pin "1") (pinfunction "1_1") (pintype "passive"))
      (node (ref "RS4") (pin "1") (pinfunction "1_1") (pintype "passive"))
      (node (ref "TP1") (pin "TP") (pinfunction "TP_TP") (pintype "input"))
      (node (ref "U1") (pin "10") (pinfunction "AVDD1_10") (pintype "bidirectional"))
      (node (ref "U1") (pin "11") (pinfunction "AVDD2_11") (pintype "bidirectional"))
      (node (ref "U1") (pin "9") (pinfunction "DVDD_9") (pintype "bidirectional"))
      (node (ref "U11") (pin "7") (pinfunction "VBAT_7") (pintype "power_in"))
      (node (ref "U11") (pin "8") (pinfunction "VDD_8") (pintype "power_in"))
      (node (ref "U13") (pin "13") (pinfunction "VDD_13") (pintype "power_in"))
      (node (ref "U13") (pin "14") (pinfunction "VDD1_14") (pintype "power_in"))
      (node (ref "U14") (pin "13") (pinfunction "VDD_13") (pintype "power_in"))
      (node (ref "U14") (pin "14") (pinfunction "VDD1_14") (pintype "power_in"))
      (node (ref "U15") (pin "2") (pinfunction "VDD_2") (pintype "power_in"))
      (node (ref "U2") (pin "5") (pinfunction "EN_5") (pintype "input"))
      (node (ref "U2") (pin "6") (pinfunction "VDD_6") (pintype "power_in"))
      (node (ref "U3") (pin "8") (pinfunction "V+_8") (pintype "power_in"))
      (node (ref "U4") (pin "8") (pinfunction "VCC_8") (pintype "power_in"))
      (node (ref "U5") (pin "1") (pinfunction "VDD_1") (pintype "power_in"))
      (node (ref "U5") (pin "18") (pinfunction "EN_18") (pintype "input"))
      (node (ref "U6") (pin "22") (pinfunction "AVDD33_22") (pintype "power_in"))
      (node (ref "U6") (pin "32") (pinfunction "IOVDD33__32") (pintype "power_in"))
      (node (ref "U6") (pin "48") (pinfunction "IOVDD33_48") (pintype "power_in"))
      (node (ref "U8") (pin "3") (pinfunction "~{WP}_3") (pintype "input"))
      (node (ref "U8") (pin "7") (pinfunction "~{HOLD}_7") (pintype "input"))
      (node (ref "U8") (pin "8") (pinfunction "VDD_8") (pintype "power_in"))
      (node (ref "U9") (pin "3") (pinfunction "~{WP}_3") (pintype "input"))
      (node (ref "U9") (pin "7") (pinfunction "~{HOLD}_7") (pintype "input"))
      (node (ref "U9") (pin "8") (pinfunction "VDD_8") (pintype "power_in"))
    )
    (net (code "150") (name "VCC{slash}2") (class "Default")
      (node (ref "C26") (pin "2") (pinfunction "2_2") (pintype "passive"))
      (node (ref "R16") (pin "1") (pinfunction "1_1") (pintype "passive"))
      (node (ref "R17") (pin "2") (pinfunction "2_2") (pintype "passive"))
      (node (ref "R20") (pin "2") (pinfunction "2_2") (pintype "passive"))
      (node (ref "TP9") (pin "TP") (pinfunction "TP_TP") (pintype "input"))
      (node (ref "U3") (pin "3") (pinfunction "IN+_3") (pintype "input"))
      (node (ref "U3") (pin "5") (pinfunction "IN+_5") (pintype "input"))
    )
    (net (code "151") (name "VDD") (class "Default")
      (node (ref "JP2") (pin "22") (pinfunction "22_22") (pintype "passive"))
      (node (ref "JP3") (pin "2") (pinfunction "2_2") (pintype "passive"))
      (node (ref "JP7") (pin "4") (pinfunction "4_4") (pintype "passive"))
      (node (ref "S1") (pin "3") (pinfunction "1_3") (pintype "passive"))
      (node (ref "S1") (pin "4") (pinfunction "1_4") (pintype "passive"))
    )
    (net (code "152") (name "VIN") (class "Default")
      (node (ref "R18") (pin "1") (pinfunction "1_1") (pintype "passive"))
      (node (ref "R19") (pin "2") (pinfunction "2_2") (pintype "passive"))
      (node (ref "U1") (pin "5") (pinfunction "VIN_5") (pintype "bidirectional"))
    )
    (net (code "153") (name "VOUT") (class "Default")
      (node (ref "C25") (pin "2") (pinfunction "2_2") (pintype "passive"))
      (node (ref "TP3") (pin "TP") (pinfunction "TP_TP") (pintype "input"))
      (node (ref "U1") (pin "6") (pinfunction "VOUT_6") (pintype "bidirectional"))
    )
    (net (code "154") (name "unconnected-(JP1-Pad3)") (class "Default")
      (node (ref "JP1") (pin "3") (pinfunction "3_3") (pintype "passive"))
    )
    (net (code "155") (name "unconnected-(JP1-Pad4)") (class "Default")
      (node (ref "JP1") (pin "4") (pinfunction "4_4") (pintype "passive"))
    )
    (net (code "156") (name "unconnected-(JP1-Pad5)") (class "Default")
      (node (ref "JP1") (pin "5") (pinfunction "5_5") (pintype "passive"))
    )
    (net (code "157") (name "unconnected-(JP1-Pad8)") (class "Default")
      (node (ref "JP1") (pin "8") (pinfunction "8_8") (pintype "passive"))
    )
    (net (code "158") (name "unconnected-(JP1-Pad9)") (class "Default")
      (node (ref "JP1") (pin "9") (pinfunction "9_9") (pintype "passive"))
    )
    (net (code "159") (name "unconnected-(JP1-Pad13)") (class "Default")
      (node (ref "JP1") (pin "13") (pinfunction "13_13") (pintype "passive"))
    )
    (net (code "160") (name "unconnected-(JP1-Pad15)") (class "Default")
      (node (ref "JP1") (pin "15") (pinfunction "15_15") (pintype "passive"))
    )
    (net (code "161") (name "unconnected-(JP1-Pad16)") (class "Default")
      (node (ref "JP1") (pin "16") (pinfunction "16_16") (pintype "passive"))
    )
    (net (code "162") (name "unconnected-(JP1-Pad18)") (class "Default")
      (node (ref "JP1") (pin "18") (pinfunction "18_18") (pintype "passive"))
    )
    (net (code "163") (name "unconnected-(JP1-Pad21)") (class "Default")
      (node (ref "JP1") (pin "21") (pinfunction "21_21") (pintype "passive"))
    )
    (net (code "164") (name "unconnected-(JP1-Pad22)") (class "Default")
      (node (ref "JP1") (pin "22") (pinfunction "22_22") (pintype "passive"))
    )
    (net (code "165") (name "unconnected-(JP1-Pad23)") (class "Default")
      (node (ref "JP1") (pin "23") (pinfunction "23_23") (pintype "passive"))
    )
    (net (code "166") (name "unconnected-(JP1-Pad24)") (class "Default")
      (node (ref "JP1") (pin "24") (pinfunction "24_24") (pintype "passive"))
    )
    (net (code "167") (name "unconnected-(JP1-Pad25)") (class "Default")
      (node (ref "JP1") (pin "25") (pinfunction "25_25") (pintype "passive"))
    )
    (net (code "168") (name "unconnected-(JP1-Pad26)") (class "Default")
      (node (ref "JP1") (pin "26") (pinfunction "26_26") (pintype "passive"))
    )
    (net (code "169") (name "unconnected-(JP1-Pad27)") (class "Default")
      (node (ref "JP1") (pin "27") (pinfunction "27_27") (pintype "passive"))
    )
    (net (code "170") (name "unconnected-(JP1-Pad28)") (class "Default")
      (node (ref "JP1") (pin "28") (pinfunction "28_28") (pintype "passive"))
    )
    (net (code "171") (name "unconnected-(JP1-Pad29)") (class "Default")
      (node (ref "JP1") (pin "29") (pinfunction "29_29") (pintype "passive"))
    )
    (net (code "172") (name "unconnected-(JP1-Pad30)") (class "Default")
      (node (ref "JP1") (pin "30") (pinfunction "30_30") (pintype "passive"))
    )
    (net (code "173") (name "unconnected-(JP1-Pad31)") (class "Default")
      (node (ref "JP1") (pin "31") (pinfunction "31_31") (pintype "passive"))
    )
    (net (code "174") (name "unconnected-(JP1-Pad32)") (class "Default")
      (node (ref "JP1") (pin "32") (pinfunction "32_32") (pintype "passive"))
    )
    (net (code "175") (name "unconnected-(JP1-Pad33)") (class "Default")
      (node (ref "JP1") (pin "33") (pinfunction "33_33") (pintype "passive"))
    )
    (net (code "176") (name "unconnected-(JP1-Pad34)") (class "Default")
      (node (ref "JP1") (pin "34") (pinfunction "34_34") (pintype "passive"))
    )
    (net (code "177") (name "unconnected-(JP1-Pad42)") (class "Default")
      (node (ref "JP1") (pin "42") (pinfunction "42_42") (pintype "passive"))
    )
    (net (code "178") (name "unconnected-(JP1-Pad43)") (class "Default")
      (node (ref "JP1") (pin "43") (pinfunction "43_43") (pintype "passive"))
    )
    (net (code "179") (name "unconnected-(JP1-Pad44)") (class "Default")
      (node (ref "JP1") (pin "44") (pinfunction "44_44") (pintype "passive"))
    )
    (net (code "180") (name "unconnected-(JP1-Pad45)") (class "Default")
      (node (ref "JP1") (pin "45") (pinfunction "45_45") (pintype "passive"))
    )
    (net (code "181") (name "unconnected-(JP1-Pad46)") (class "Default")
      (node (ref "JP1") (pin "46") (pinfunction "46_46") (pintype "passive"))
    )
    (net (code "182") (name "unconnected-(JP1-Pad47)") (class "Default")
      (node (ref "JP1") (pin "47") (pinfunction "47_47") (pintype "passive"))
    )
    (net (code "183") (name "unconnected-(JP1-Pad48)") (class "Default")
      (node (ref "JP1") (pin "48") (pinfunction "48_48") (pintype "passive"))
    )
    (net (code "184") (name "unconnected-(JP2-Pad7)") (class "Default")
      (node (ref "JP2") (pin "7") (pinfunction "7_7") (pintype "passive"))
    )
    (net (code "185") (name "unconnected-(JP2-Pad8)") (class "Default")
      (node (ref "JP2") (pin "8") (pinfunction "8_8") (pintype "passive"))
    )
    (net (code "186") (name "unconnected-(JP2-Pad9)") (class "Default")
      (node (ref "JP2") (pin "9") (pinfunction "9_9") (pintype "passive"))
    )
    (net (code "187") (name "unconnected-(JP2-Pad10)") (class "Default")
      (node (ref "JP2") (pin "10") (pinfunction "10_10") (pintype "passive"))
    )
    (net (code "188") (name "unconnected-(JP2-Pad12)") (class "Default")
      (node (ref "JP2") (pin "12") (pinfunction "12_12") (pintype "passive"))
    )
    (net (code "189") (name "unconnected-(JP2-Pad16)") (class "Default")
      (node (ref "JP2") (pin "16") (pinfunction "16_16") (pintype "passive"))
    )
    (net (code "190") (name "unconnected-(JP2-Pad17)") (class "Default")
      (node (ref "JP2") (pin "17") (pinfunction "17_17") (pintype "passive"))
    )
    (net (code "191") (name "unconnected-(JP2-Pad18)") (class "Default")
      (node (ref "JP2") (pin "18") (pinfunction "18_18") (pintype "passive"))
    )
    (net (code "192") (name "unconnected-(JP2-Pad21)") (class "Default")
      (node (ref "JP2") (pin "21") (pinfunction "21_21") (pintype "passive"))
    )
    (net (code "193") (name "unconnected-(JP2-Pad27)") (class "Default")
      (node (ref "JP2") (pin "27") (pinfunction "27_27") (pintype "passive"))
    )
    (net (code "194") (name "unconnected-(JP2-Pad28)") (class "Default")
      (node (ref "JP2") (pin "28") (pinfunction "28_28") (pintype "passive"))
    )
    (net (code "195") (name "unconnected-(JP2-Pad29)") (class "Default")
      (node (ref "JP2") (pin "29") (pinfunction "29_29") (pintype "passive"))
    )
    (net (code "196") (name "unconnected-(JP2-Pad30)") (class "Default")
      (node (ref "JP2") (pin "30") (pinfunction "30_30") (pintype "passive"))
    )
    (net (code "197") (name "unconnected-(JP2-Pad31)") (class "Default")
      (node (ref "JP2") (pin "31") (pinfunction "31_31") (pintype "passive"))
    )
    (net (code "198") (name "unconnected-(JP2-Pad32)") (class "Default")
      (node (ref "JP2") (pin "32") (pinfunction "32_32") (pintype "passive"))
    )
    (net (code "199") (name "unconnected-(JP2-Pad39)") (class "Default")
      (node (ref "JP2") (pin "39") (pinfunction "39_39") (pintype "passive"))
    )
    (net (code "200") (name "unconnected-(JP2-Pad40)") (class "Default")
      (node (ref "JP2") (pin "40") (pinfunction "40_40") (pintype "passive"))
    )
    (net (code "201") (name "unconnected-(JP2-Pad41)") (class "Default")
      (node (ref "JP2") (pin "41") (pinfunction "41_41") (pintype "passive"))
    )
    (net (code "202") (name "unconnected-(JP2-Pad42)") (class "Default")
      (node (ref "JP2") (pin "42") (pinfunction "42_42") (pintype "passive"))
    )
    (net (code "203") (name "unconnected-(JP2-Pad43)") (class "Default")
      (node (ref "JP2") (pin "43") (pinfunction "43_43") (pintype "passive"))
    )
    (net (code "204") (name "unconnected-(JP2-Pad45)") (class "Default")
      (node (ref "JP2") (pin "45") (pinfunction "45_45") (pintype "passive"))
    )
    (net (code "205") (name "unconnected-(JP2-Pad47)") (class "Default")
      (node (ref "JP2") (pin "47") (pinfunction "47_47") (pintype "passive"))
    )
    (net (code "206") (name "unconnected-(JP2-Pad48)") (class "Default")
      (node (ref "JP2") (pin "48") (pinfunction "48_48") (pintype "passive"))
    )
    (net (code "207") (name "unconnected-(U5-S9-Pad11)") (class "Default")
      (node (ref "U5") (pin "11") (pinfunction "S9_11") (pintype "bidirectional"))
    )
    (net (code "208") (name "unconnected-(U5-S10-Pad10)") (class "Default")
      (node (ref "U5") (pin "10") (pinfunction "S10_10") (pintype "bidirectional"))
    )
    (net (code "209") (name "unconnected-(U5-S11-Pad9)") (class "Default")
      (node (ref "U5") (pin "9") (pinfunction "S11_9") (pintype "bidirectional"))
    )
    (net (code "210") (name "unconnected-(U5-S12-Pad8)") (class "Default")
      (node (ref "U5") (pin "8") (pinfunction "S12_8") (pintype "bidirectional"))
    )
    (net (code "211") (name "unconnected-(U5-S13-Pad7)") (class "Default")
      (node (ref "U5") (pin "7") (pinfunction "S13_7") (pintype "bidirectional"))
    )
    (net (code "212") (name "unconnected-(U5-S14-Pad6)") (class "Default")
      (node (ref "U5") (pin "6") (pinfunction "S14_6") (pintype "bidirectional"))
    )
    (net (code "213") (name "unconnected-(U5-S15-Pad5)") (class "Default")
      (node (ref "U5") (pin "5") (pinfunction "S15_5") (pintype "bidirectional"))
    )
    (net (code "214") (name "unconnected-(U5-S16-Pad4)") (class "Default")
      (node (ref "U5") (pin "4") (pinfunction "S16_4") (pintype "bidirectional"))
    )
    (net (code "215") (name "unconnected-(U6-COL-Pad42)") (class "Default")
      (node (ref "U6") (pin "42") (pinfunction "COL_42") (pintype "output"))
    )
    (net (code "216") (name "unconnected-(U6-LED_SPEED-Pad27)") (class "Default")
      (node (ref "U6") (pin "27") (pinfunction "LED_SPEED_27") (pintype "output"))
    )
    (net (code "217") (name "unconnected-(U6-PWRDN_INTN-Pad7)") (class "Default")
      (node (ref "U6") (pin "7") (pinfunction "PWRDN_INTN_7") (pintype "bidirectional"))
    )
    (net (code "218") (name "unconnected-(U6-RXD_2-Pad45)") (class "Default")
      (node (ref "U6") (pin "45") (pinfunction "RXD_2_45") (pintype "output"))
    )
    (net (code "219") (name "unconnected-(U6-RXD_3-Pad46)") (class "Default")
      (node (ref "U6") (pin "46") (pinfunction "RXD_3_46") (pintype "output"))
    )
    (net (code "220") (name "unconnected-(U6-RX_CLK-Pad38)") (class "Default")
      (node (ref "U6") (pin "38") (pinfunction "RX_CLK_38") (pintype "output"))
    )
    (net (code "221") (name "unconnected-(U6-RX_ER-Pad41)") (class "Default")
      (node (ref "U6") (pin "41") (pinfunction "RX_ER_41") (pintype "output"))
    )
    (net (code "222") (name "unconnected-(U6-TXD_2-Pad5)") (class "Default")
      (node (ref "U6") (pin "5") (pinfunction "TXD_2_5") (pintype "input"))
    )
    (net (code "223") (name "unconnected-(U6-TXD_3-Pad6)") (class "Default")
      (node (ref "U6") (pin "6") (pinfunction "TXD_3_6") (pintype "input"))
    )
    (net (code "224") (name "unconnected-(U6-TX_CLK-Pad1)") (class "Default")
      (node (ref "U6") (pin "1") (pinfunction "TX_CLK_1") (pintype "output"))
    )
    (net (code "225") (name "unconnected-(U6-X2-Pad33)") (class "Default")
      (node (ref "U6") (pin "33") (pinfunction "X2_33") (pintype "output"))
    )
    (net (code "226") (name "~{RST}") (class "Default")
      (node (ref "JP1") (pin "6") (pinfunction "6_6") (pintype "passive"))
      (node (ref "S2") (pin "1") (pinfunction "0_1") (pintype "passive"))
      (node (ref "S2") (pin "2") (pinfunction "0_2") (pintype "passive"))
    )
  )
)
